# homeboard6.net
KiCad netlist of a schematic drawn in EAGLE
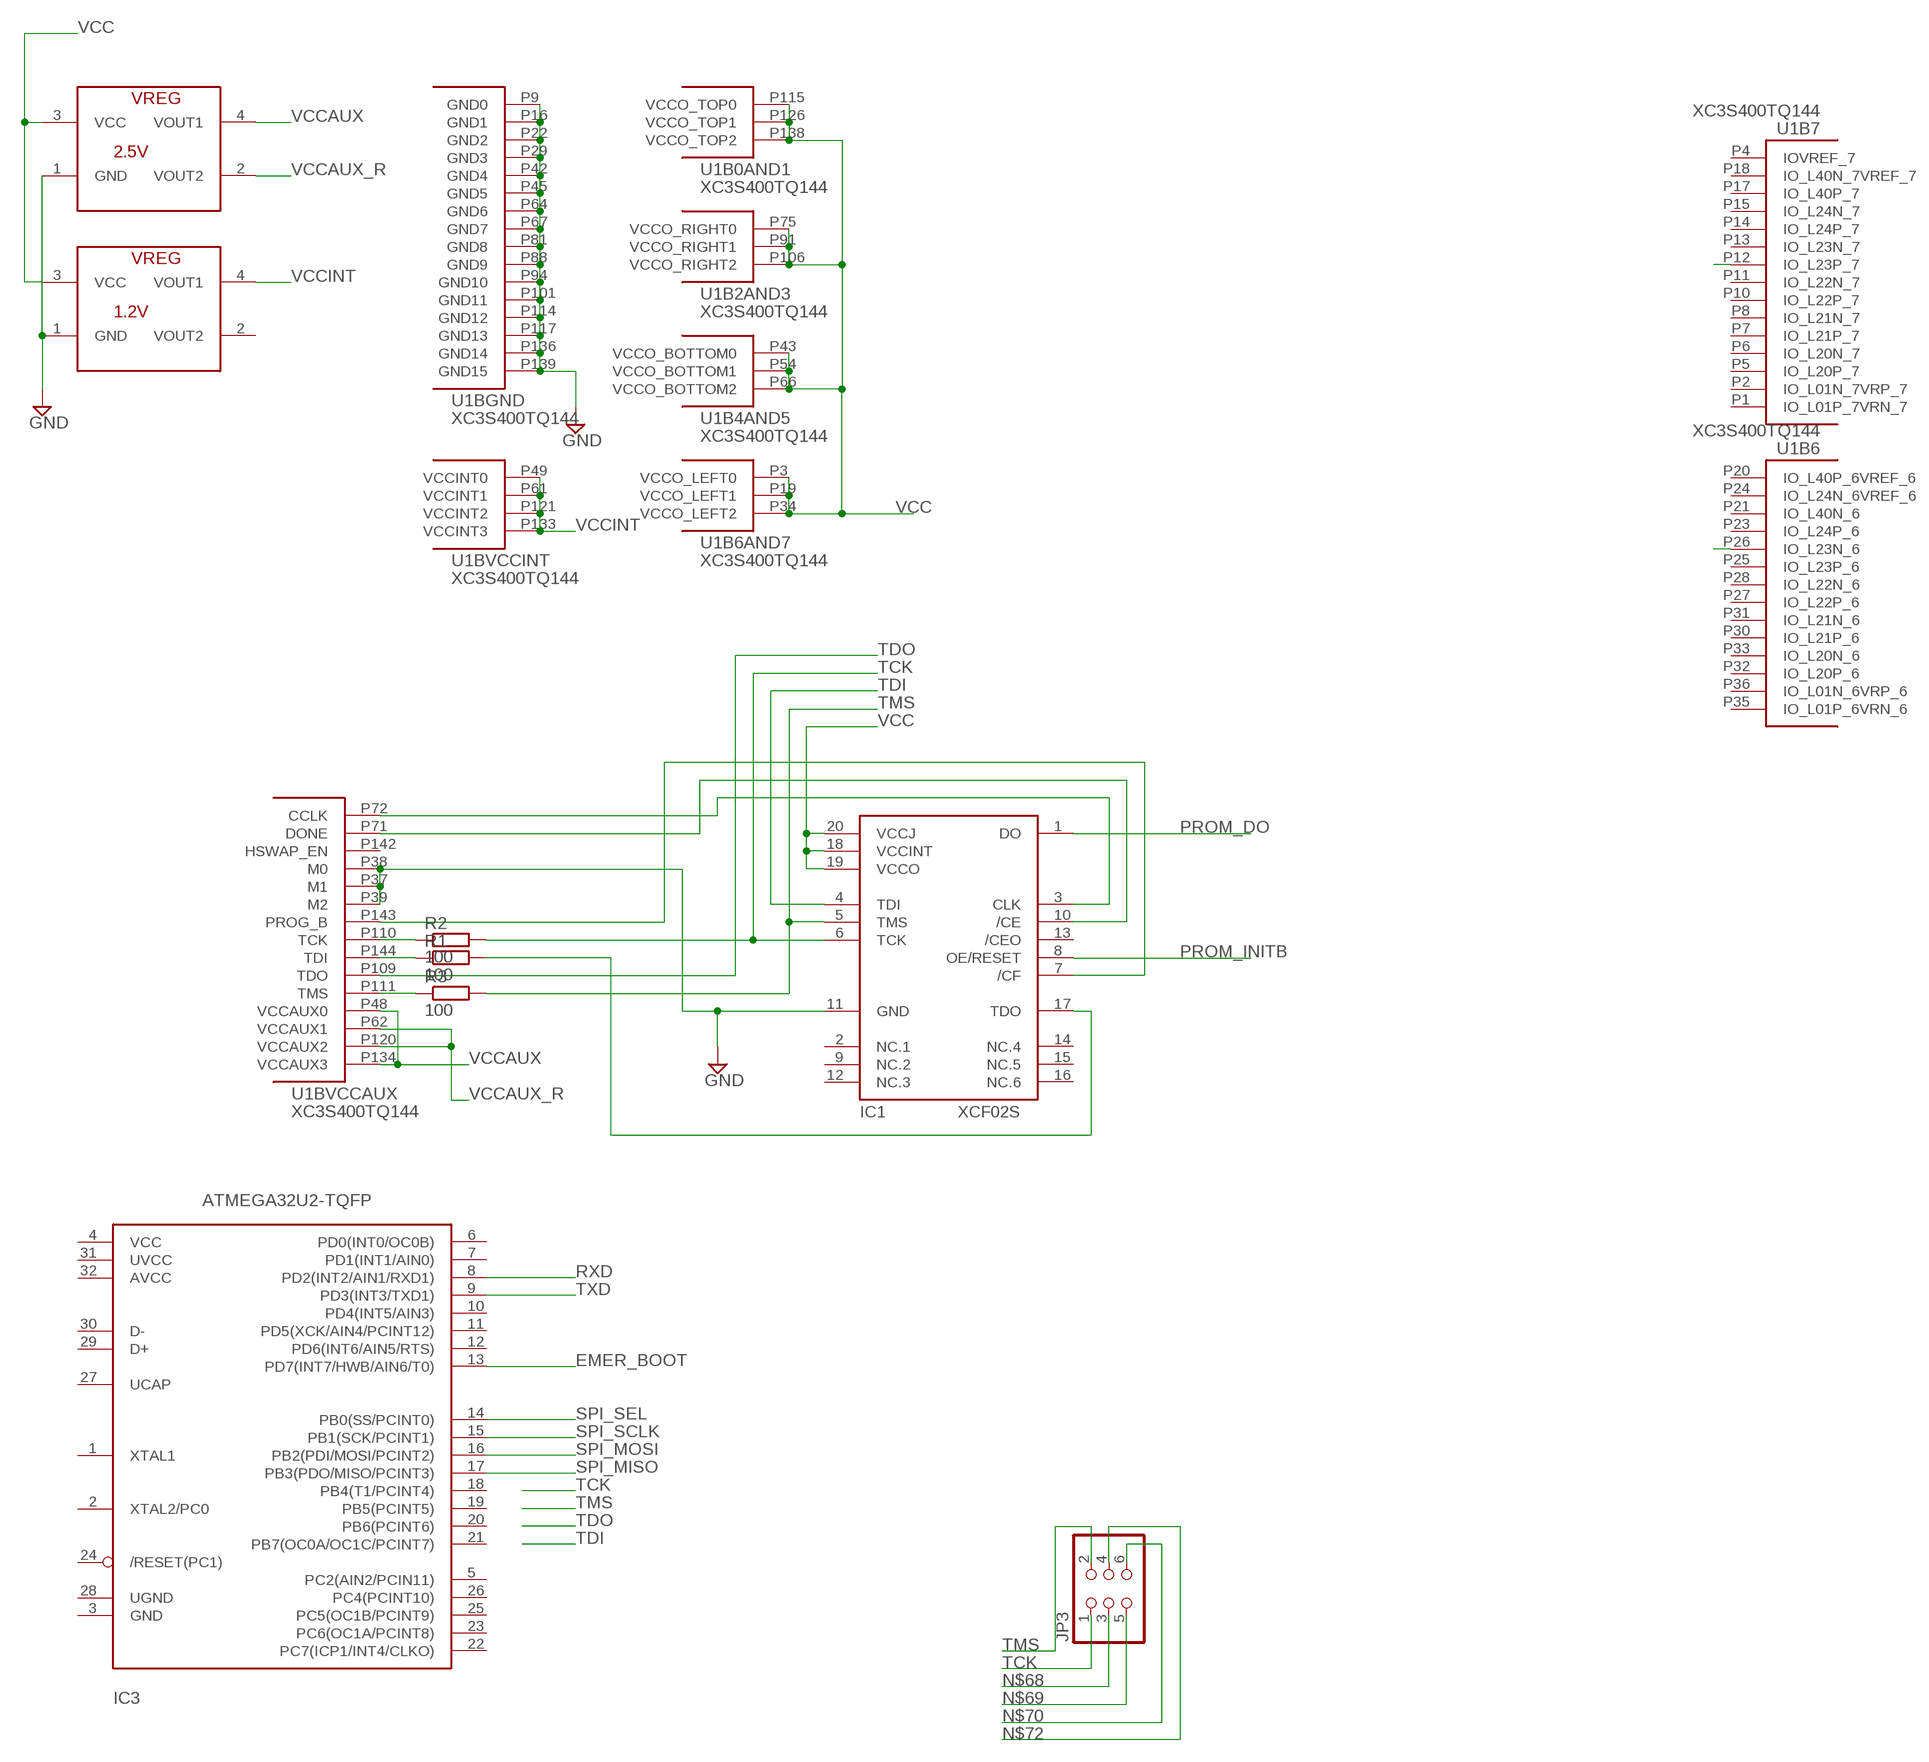
[diagram p0: schematic, sheet 1, part 1 of 3]
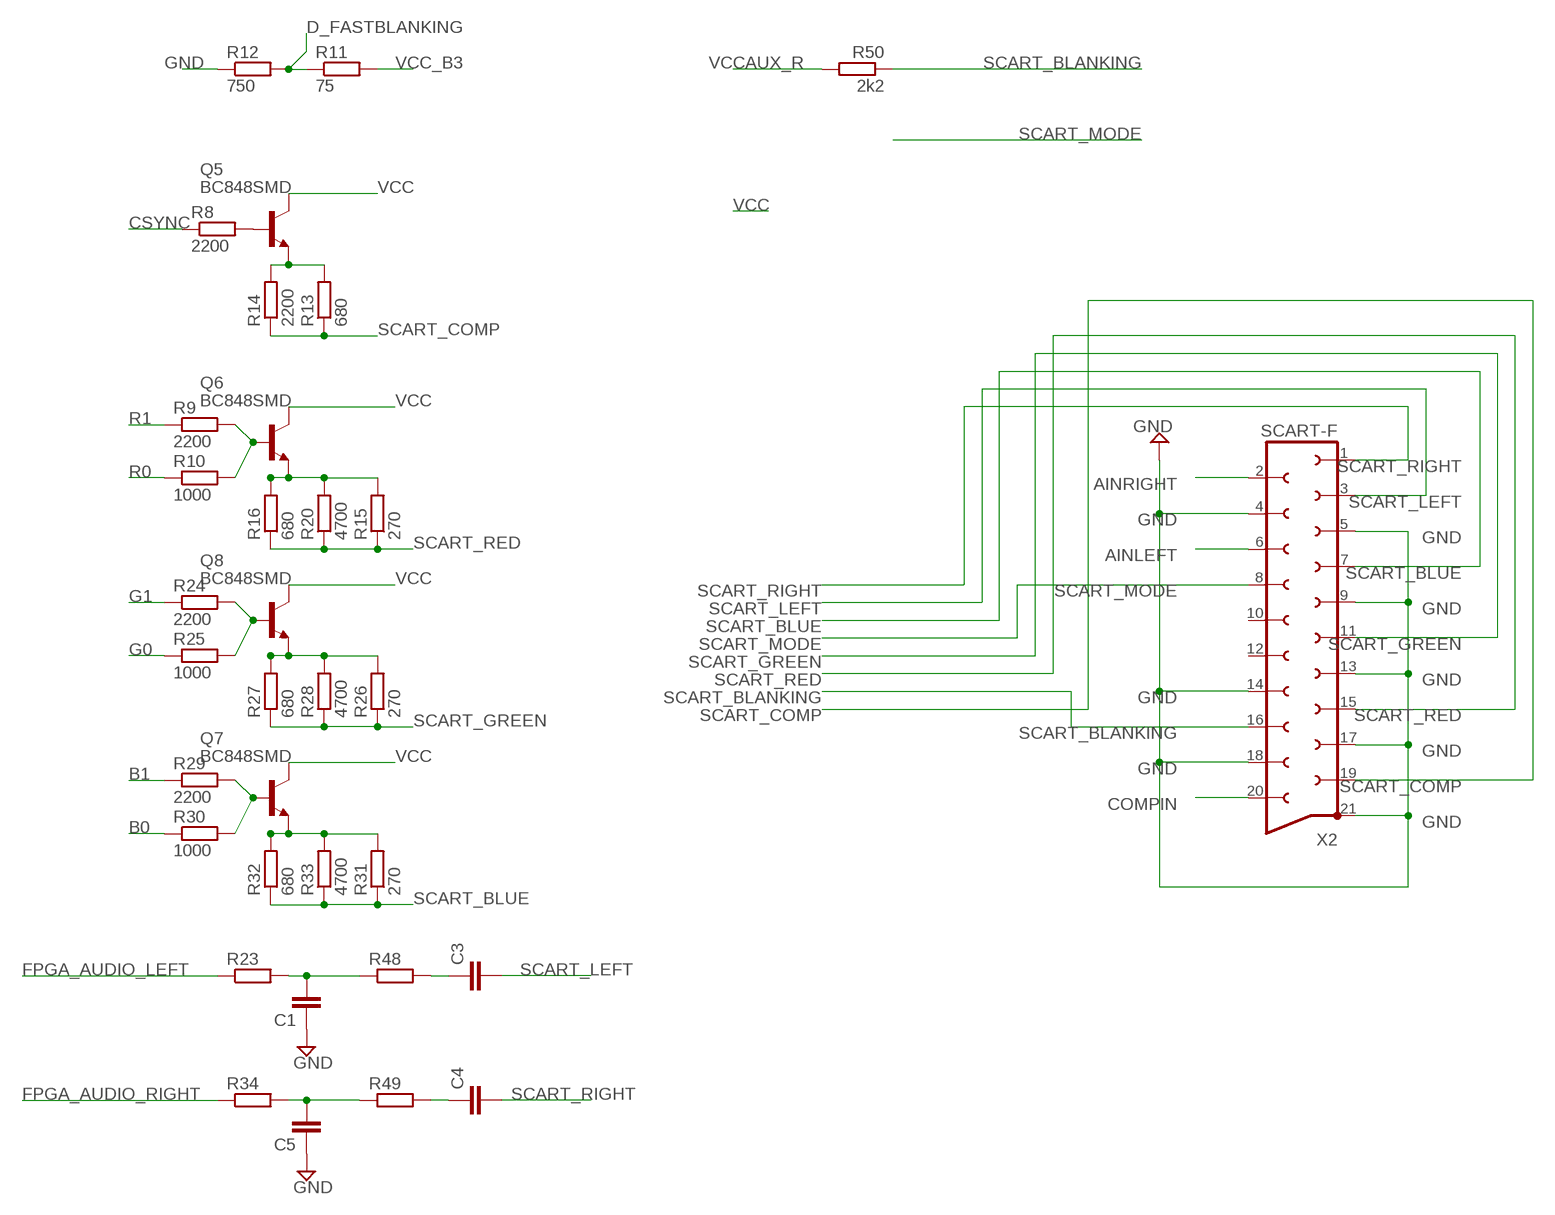
[diagram p1: schematic, sheet 1, part 2 of 3]
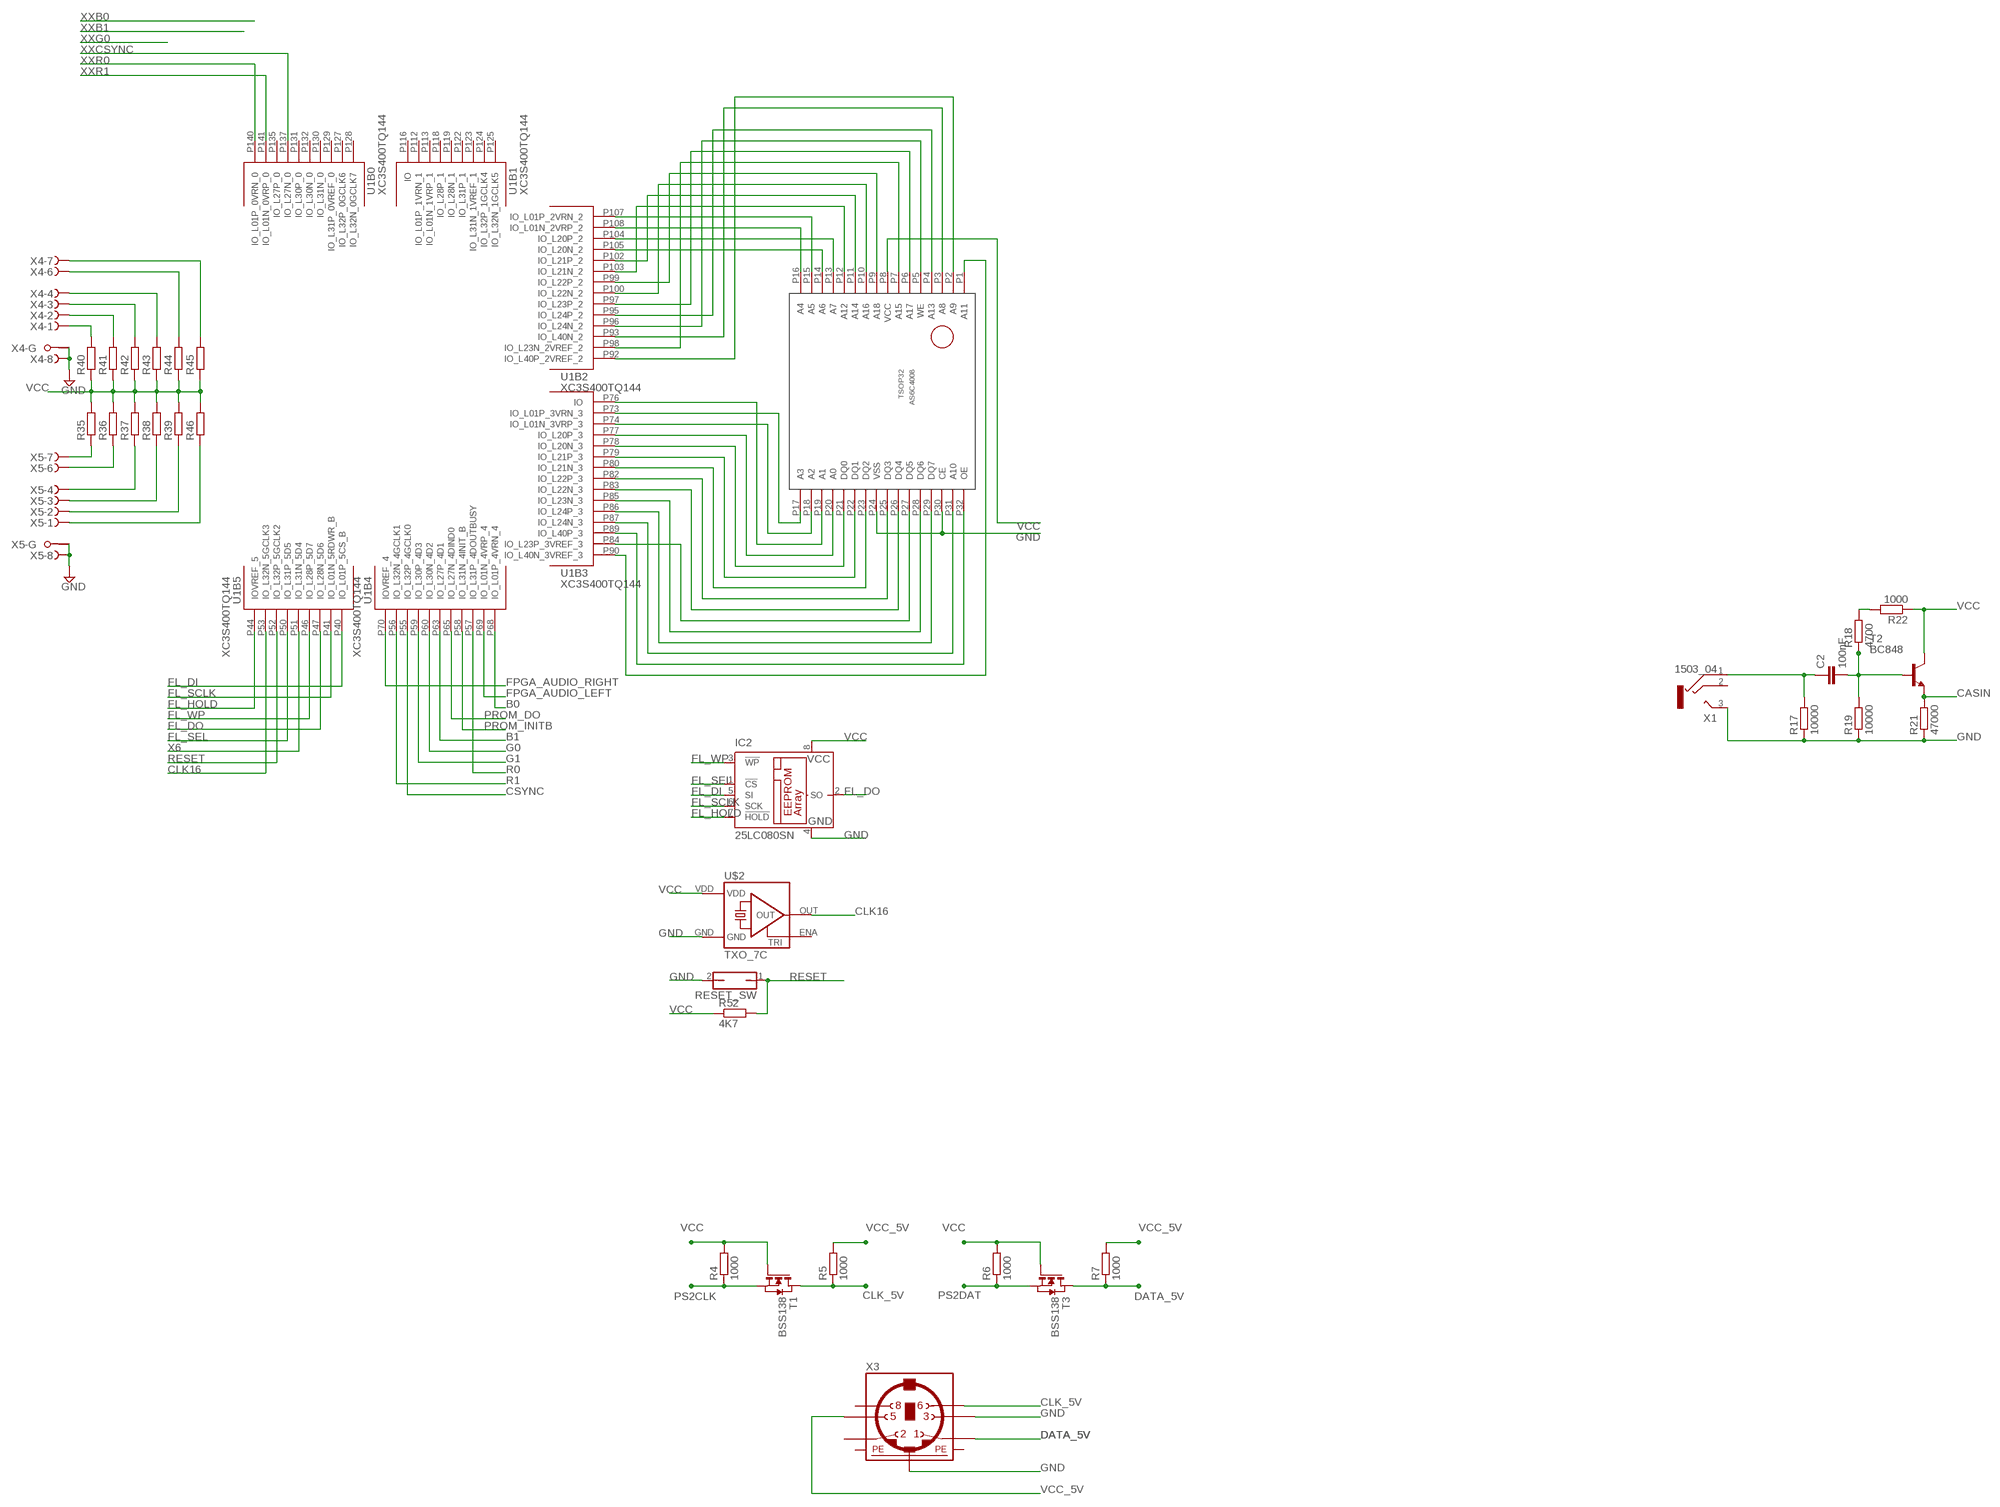
[diagram p2: schematic, sheet 1, part 3 of 3]

(export (version "E")
  (design (tool "Eeschema 10.0.6"))
  (components
    (comp (ref "C1")
      (value "C-EUC0603")
      (footprint "eagle-import:C0603")
      (libsource (lib "eagle-import") (part "C-EUC0603"))
    )
    (comp (ref "C2")
      (value "100nF")
      (footprint "eagle-import:C0603")
      (libsource (lib "eagle-import") (part "C-EUC0603"))
    )
    (comp (ref "C3")
      (value "C-EUC0603")
      (footprint "eagle-import:C0603")
      (libsource (lib "eagle-import") (part "C-EUC0603"))
    )
    (comp (ref "C4")
      (value "C-EUC0603")
      (footprint "eagle-import:C0603")
      (libsource (lib "eagle-import") (part "C-EUC0603"))
    )
    (comp (ref "C5")
      (value "C-EUC0603")
      (footprint "eagle-import:C0603")
      (libsource (lib "eagle-import") (part "C-EUC0603"))
    )
    (comp (ref "IC1")
      (value "XCF02S")
      (footprint "eagle-import:VO20")
      (libsource (lib "eagle-import") (part "XCF02S"))
    )
    (comp (ref "IC2")
      (value "25LC080SN")
      (footprint "eagle-import:SO-08")
      (fields (field (name "MF") "MICROCHIP") (field (name "MPN") "25LC080/SN"))
      (libsource (lib "eagle-import") (part "25SNLC080"))
    )
    (comp (ref "IC3")
      (value "ATMEGA32U2-TQFP")
      (footprint "eagle-import:TQFP32-08")
      (libsource (lib "eagle-import") (part "ATMEGA32U2-TQFP"))
    )
    (comp (ref "JP3")
      (value "PINHD-2X3")
      (footprint "eagle-import:2X03")
      (libsource (lib "eagle-import") (part "PINHD-2X3"))
    )
    (comp (ref "Q5")
      (value "BC848SMD")
      (footprint "eagle-import:SOT23")
      (libsource (lib "eagle-import") (part "BC848SMD"))
    )
    (comp (ref "Q6")
      (value "BC848SMD")
      (footprint "eagle-import:SOT23")
      (libsource (lib "eagle-import") (part "BC848SMD"))
    )
    (comp (ref "Q7")
      (value "BC848SMD")
      (footprint "eagle-import:SOT23")
      (libsource (lib "eagle-import") (part "BC848SMD"))
    )
    (comp (ref "Q8")
      (value "BC848SMD")
      (footprint "eagle-import:SOT23")
      (libsource (lib "eagle-import") (part "BC848SMD"))
    )
    (comp (ref "R1")
      (value "100")
      (footprint "eagle-import:R0805")
      (libsource (lib "eagle-import") (part "R-EU_R0805"))
    )
    (comp (ref "R2")
      (value "100")
      (footprint "eagle-import:R0805")
      (libsource (lib "eagle-import") (part "R-EU_R0805"))
    )
    (comp (ref "R3")
      (value "100")
      (footprint "eagle-import:R0805")
      (libsource (lib "eagle-import") (part "R-EU_R0805"))
    )
    (comp (ref "R4")
      (value "1000")
      (footprint "eagle-import:R0805")
      (libsource (lib "eagle-import") (part "R-EU_R0805"))
    )
    (comp (ref "R5")
      (value "1000")
      (footprint "eagle-import:R0805")
      (libsource (lib "eagle-import") (part "R-EU_R0805"))
    )
    (comp (ref "R6")
      (value "1000")
      (footprint "eagle-import:R0805")
      (libsource (lib "eagle-import") (part "R-EU_R0805"))
    )
    (comp (ref "R7")
      (value "1000")
      (footprint "eagle-import:R0805")
      (libsource (lib "eagle-import") (part "R-EU_R0805"))
    )
    (comp (ref "R8")
      (value "2200")
      (footprint "eagle-import:R0805")
      (libsource (lib "eagle-import") (part "R-EU_R0805"))
    )
    (comp (ref "R9")
      (value "2200")
      (footprint "eagle-import:R0805")
      (libsource (lib "eagle-import") (part "R-EU_R0805"))
    )
    (comp (ref "R10")
      (value "1000")
      (footprint "eagle-import:R0805")
      (libsource (lib "eagle-import") (part "R-EU_R0805"))
    )
    (comp (ref "R11")
      (value "75")
      (footprint "eagle-import:R0805")
      (libsource (lib "eagle-import") (part "R-EU_R0805"))
    )
    (comp (ref "R12")
      (value "750")
      (footprint "eagle-import:R0805")
      (libsource (lib "eagle-import") (part "R-EU_R0805"))
    )
    (comp (ref "R13")
      (value "680")
      (footprint "eagle-import:R0805")
      (libsource (lib "eagle-import") (part "R-EU_R0805"))
    )
    (comp (ref "R14")
      (value "2200")
      (footprint "eagle-import:R0805")
      (libsource (lib "eagle-import") (part "R-EU_R0805"))
    )
    (comp (ref "R15")
      (value "270")
      (footprint "eagle-import:R0805")
      (libsource (lib "eagle-import") (part "R-EU_R0805"))
    )
    (comp (ref "R16")
      (value "680")
      (footprint "eagle-import:R0805")
      (libsource (lib "eagle-import") (part "R-EU_R0805"))
    )
    (comp (ref "R17")
      (value "10000")
      (footprint "eagle-import:R0805")
      (libsource (lib "eagle-import") (part "R-EU_R0805"))
    )
    (comp (ref "R18")
      (value "4700")
      (footprint "eagle-import:R0805")
      (libsource (lib "eagle-import") (part "R-EU_R0805"))
    )
    (comp (ref "R19")
      (value "10000")
      (footprint "eagle-import:R0805")
      (libsource (lib "eagle-import") (part "R-EU_R0805"))
    )
    (comp (ref "R20")
      (value "4700")
      (footprint "eagle-import:R0805")
      (libsource (lib "eagle-import") (part "R-EU_R0805"))
    )
    (comp (ref "R21")
      (value "47000")
      (footprint "eagle-import:R0805")
      (libsource (lib "eagle-import") (part "R-EU_R0805"))
    )
    (comp (ref "R22")
      (value "1000")
      (footprint "eagle-import:R0805")
      (libsource (lib "eagle-import") (part "R-EU_R0805"))
    )
    (comp (ref "R23")
      (value "R-EU_M0805")
      (footprint "eagle-import:M0805")
      (libsource (lib "eagle-import") (part "resistor_R-EU_M0805"))
    )
    (comp (ref "R24")
      (value "2200")
      (footprint "eagle-import:R0805")
      (libsource (lib "eagle-import") (part "R-EU_R0805"))
    )
    (comp (ref "R25")
      (value "1000")
      (footprint "eagle-import:R0805")
      (libsource (lib "eagle-import") (part "R-EU_R0805"))
    )
    (comp (ref "R26")
      (value "270")
      (footprint "eagle-import:R0805")
      (libsource (lib "eagle-import") (part "R-EU_R0805"))
    )
    (comp (ref "R27")
      (value "680")
      (footprint "eagle-import:R0805")
      (libsource (lib "eagle-import") (part "R-EU_R0805"))
    )
    (comp (ref "R28")
      (value "4700")
      (footprint "eagle-import:R0805")
      (libsource (lib "eagle-import") (part "R-EU_R0805"))
    )
    (comp (ref "R29")
      (value "2200")
      (footprint "eagle-import:R0805")
      (libsource (lib "eagle-import") (part "R-EU_R0805"))
    )
    (comp (ref "R30")
      (value "1000")
      (footprint "eagle-import:R0805")
      (libsource (lib "eagle-import") (part "R-EU_R0805"))
    )
    (comp (ref "R31")
      (value "270")
      (footprint "eagle-import:R0805")
      (libsource (lib "eagle-import") (part "R-EU_R0805"))
    )
    (comp (ref "R32")
      (value "680")
      (footprint "eagle-import:R0805")
      (libsource (lib "eagle-import") (part "R-EU_R0805"))
    )
    (comp (ref "R33")
      (value "4700")
      (footprint "eagle-import:R0805")
      (libsource (lib "eagle-import") (part "R-EU_R0805"))
    )
    (comp (ref "R34")
      (value "R-EU_M0805")
      (footprint "eagle-import:M0805")
      (libsource (lib "eagle-import") (part "resistor_R-EU_M0805"))
    )
    (comp (ref "R35")
      (value "R-EU_M0805")
      (footprint "eagle-import:M0805")
      (libsource (lib "eagle-import") (part "resistor_R-EU_M0805"))
    )
    (comp (ref "R36")
      (value "R-EU_M0805")
      (footprint "eagle-import:M0805")
      (libsource (lib "eagle-import") (part "resistor_R-EU_M0805"))
    )
    (comp (ref "R37")
      (value "R-EU_M0805")
      (footprint "eagle-import:M0805")
      (libsource (lib "eagle-import") (part "resistor_R-EU_M0805"))
    )
    (comp (ref "R38")
      (value "R-EU_M0805")
      (footprint "eagle-import:M0805")
      (libsource (lib "eagle-import") (part "resistor_R-EU_M0805"))
    )
    (comp (ref "R39")
      (value "R-EU_M0805")
      (footprint "eagle-import:M0805")
      (libsource (lib "eagle-import") (part "resistor_R-EU_M0805"))
    )
    (comp (ref "R40")
      (value "R-EU_M0805")
      (footprint "eagle-import:M0805")
      (libsource (lib "eagle-import") (part "resistor_R-EU_M0805"))
    )
    (comp (ref "R41")
      (value "R-EU_M0805")
      (footprint "eagle-import:M0805")
      (libsource (lib "eagle-import") (part "resistor_R-EU_M0805"))
    )
    (comp (ref "R42")
      (value "R-EU_M0805")
      (footprint "eagle-import:M0805")
      (libsource (lib "eagle-import") (part "resistor_R-EU_M0805"))
    )
    (comp (ref "R43")
      (value "R-EU_M0805")
      (footprint "eagle-import:M0805")
      (libsource (lib "eagle-import") (part "resistor_R-EU_M0805"))
    )
    (comp (ref "R44")
      (value "R-EU_M0805")
      (footprint "eagle-import:M0805")
      (libsource (lib "eagle-import") (part "resistor_R-EU_M0805"))
    )
    (comp (ref "R45")
      (value "R-EU_M0805")
      (footprint "eagle-import:M0805")
      (libsource (lib "eagle-import") (part "resistor_R-EU_M0805"))
    )
    (comp (ref "R46")
      (value "R-EU_M0805")
      (footprint "eagle-import:M0805")
      (libsource (lib "eagle-import") (part "resistor_R-EU_M0805"))
    )
    (comp (ref "R48")
      (value "R-EU_M0805")
      (footprint "eagle-import:M0805")
      (libsource (lib "eagle-import") (part "resistor_R-EU_M0805"))
    )
    (comp (ref "R49")
      (value "R-EU_M0805")
      (footprint "eagle-import:M0805")
      (libsource (lib "eagle-import") (part "resistor_R-EU_M0805"))
    )
    (comp (ref "R50")
      (value "2k2")
      (footprint "eagle-import:M0805")
      (libsource (lib "eagle-import") (part "resistor_R-EU_M0805"))
    )
    (comp (ref "R52")
      (value "4K7")
      (footprint "eagle-import:M0805")
      (libsource (lib "eagle-import") (part "resistor_R-EU_M0805"))
    )
    (comp (ref "REG1.2")
      (value "1.2V")
      (footprint "eagle-import:SOT223")
      (libsource (lib "eagle-import") (part "NX1117"))
    )
    (comp (ref "REG2.5")
      (value "2.5V")
      (footprint "eagle-import:SOT223")
      (libsource (lib "eagle-import") (part "NX1117"))
    )
    (comp (ref "RESET_SW")
      (value "JP1Q")
      (footprint "eagle-import:JP1")
      (libsource (lib "eagle-import") (part "JP1Q"))
    )
    (comp (ref "T1")
      (value "BSS138")
      (footprint "eagle-import:SOT-23")
      (libsource (lib "eagle-import") (part "NMOSSOT23"))
    )
    (comp (ref "T2")
      (value "BC848")
      (footprint "eagle-import:SOT23")
      (libsource (lib "eagle-import") (part "BC848"))
    )
    (comp (ref "T3")
      (value "BSS138")
      (footprint "eagle-import:SOT-23")
      (libsource (lib "eagle-import") (part "NMOSSOT23"))
    )
    (comp (ref "U$1")
      (value "AS6C4008")
      (footprint "eagle-import:TSOP32")
      (libsource (lib "eagle-import") (part "AS6C4008"))
    )
    (comp (ref "U$2")
      (value "TXO_7C")
      (footprint "eagle-import:OSC_7C")
      (libsource (lib "eagle-import") (part "TXO_7C"))
    )
    (comp (ref "U1")
      (value "XC3S400TQ144")
      (footprint "eagle-import:TQ144")
      (libsource (lib "eagle-import") (part "XC3S400TQ144"))
    )
    (comp (ref "X1")
      (value "1503_04")
      (footprint "eagle-import:1503_04")
      (libsource (lib "eagle-import") (part "1503_04"))
    )
    (comp (ref "X2")
      (value "SCART-F")
      (footprint "eagle-import:SCART-F")
      (libsource (lib "eagle-import") (part "SCART-F"))
    )
    (comp (ref "X3")
      (value "MINI_DIN_6")
      (footprint "eagle-import:M_DIN6")
      (libsource (lib "eagle-import") (part "MINI_DIN_6"))
    )
    (comp (ref "X4")
      (value "F09HPS")
      (footprint "eagle-import:F09HP")
      (libsource (lib "eagle-import") (part "F09HPS"))
    )
    (comp (ref "X5")
      (value "F09HPS")
      (footprint "eagle-import:F09HP")
      (libsource (lib "eagle-import") (part "F09HPS"))
    )
  )
  (nets
    (net (code "1") (name "/AINLEFT") (class "Default")
      (node (ref "X2") (pin "6") (pinfunction "6_6") (pintype "passive"))
    )
    (net (code "2") (name "/AINRIGHT") (class "Default")
      (node (ref "X2") (pin "2") (pinfunction "2_2") (pintype "passive"))
    )
    (net (code "3") (name "/B0") (class "Default")
      (node (ref "R30") (pin "1") (pinfunction "1_1") (pintype "passive"))
      (node (ref "U1") (pin "P68") (pinfunction "IO_L01P_4VRN_4_P68") (pintype "bidirectional"))
    )
    (net (code "4") (name "/B1") (class "Default")
      (node (ref "R29") (pin "1") (pinfunction "1_1") (pintype "passive"))
      (node (ref "U1") (pin "P63") (pinfunction "IO_L27P_4D1_P63") (pintype "bidirectional"))
    )
    (net (code "5") (name "/CASIN") (class "Default")
      (node (ref "R21") (pin "2") (pinfunction "2_2") (pintype "passive"))
      (node (ref "T2") (pin "2") (pinfunction "E_2") (pintype "passive"))
    )
    (net (code "6") (name "/CLK16") (class "Default")
      (node (ref "U$2") (pin "OUT") (pinfunction "OUT_OUT") (pintype "output"))
      (node (ref "U1") (pin "P53") (pinfunction "IO_L32N_5GCLK3_P53") (pintype "bidirectional"))
    )
    (net (code "7") (name "/CLK_5V") (class "Default")
      (node (ref "R5") (pin "1") (pinfunction "1_1") (pintype "passive"))
      (node (ref "T1") (pin "1") (pinfunction "D_1") (pintype "passive"))
      (node (ref "X3") (pin "6") (pinfunction "6_6") (pintype "passive"))
    )
    (net (code "8") (name "/COMPIN") (class "Default")
      (node (ref "X2") (pin "20") (pinfunction "20_20") (pintype "passive"))
    )
    (net (code "9") (name "/CSYNC") (class "Default")
      (node (ref "R8") (pin "1") (pinfunction "1_1") (pintype "passive"))
      (node (ref "U1") (pin "P55") (pinfunction "IO_L32P_4GCLK0_P55") (pintype "bidirectional"))
    )
    (net (code "10") (name "/DATA_5V") (class "Default")
      (node (ref "R7") (pin "1") (pinfunction "1_1") (pintype "passive"))
      (node (ref "T3") (pin "1") (pinfunction "D_1") (pintype "passive"))
      (node (ref "X3") (pin "1") (pinfunction "1_1") (pintype "passive"))
    )
    (net (code "11") (name "/D_FASTBLANKING") (class "Default")
      (node (ref "R11") (pin "1") (pinfunction "1_1") (pintype "passive"))
      (node (ref "R12") (pin "2") (pinfunction "2_2") (pintype "passive"))
    )
    (net (code "12") (name "/EMER_BOOT") (class "Default")
      (node (ref "IC3") (pin "13") (pinfunction "PD7(INT7/HWB/AIN6/T0)_13") (pintype "bidirectional"))
    )
    (net (code "13") (name "/FL_DI") (class "Default")
      (node (ref "IC2") (pin "5") (pinfunction "SI_5") (pintype "input"))
      (node (ref "U1") (pin "P40") (pinfunction "IO_L01P_5CS_B_P40") (pintype "bidirectional"))
    )
    (net (code "14") (name "/FL_DO") (class "Default")
      (node (ref "IC2") (pin "2") (pinfunction "SO_2") (pintype "bidirectional"))
      (node (ref "U1") (pin "P47") (pinfunction "IO_L28N_5D6_P47") (pintype "bidirectional"))
    )
    (net (code "15") (name "/FL_HOLD") (class "Default")
      (node (ref "IC2") (pin "7") (pinfunction "~{HOLD}_7") (pintype "input"))
      (node (ref "U1") (pin "P44") (pinfunction "IOVREF_5_P44") (pintype "bidirectional"))
    )
    (net (code "16") (name "/FL_SCLK") (class "Default")
      (node (ref "IC2") (pin "6") (pinfunction "SCK_6") (pintype "input"))
      (node (ref "U1") (pin "P41") (pinfunction "IO_L01N_5RDWR_B_P41") (pintype "bidirectional"))
    )
    (net (code "17") (name "/FL_SEL") (class "Default")
      (node (ref "IC2") (pin "1") (pinfunction "~{CS}_1") (pintype "input"))
      (node (ref "U1") (pin "P50") (pinfunction "IO_L31P_5D5_P50") (pintype "bidirectional"))
    )
    (net (code "18") (name "/FL_WP") (class "Default")
      (node (ref "IC2") (pin "3") (pinfunction "~{WP}_3") (pintype "input"))
      (node (ref "U1") (pin "P46") (pinfunction "IO_L28P_5D7_P46") (pintype "bidirectional"))
    )
    (net (code "19") (name "/FPGA_AUDIO_LEFT") (class "Default")
      (node (ref "R23") (pin "1") (pinfunction "1_1") (pintype "passive"))
      (node (ref "U1") (pin "P69") (pinfunction "IO_L01N_4VRP_4_P69") (pintype "bidirectional"))
    )
    (net (code "20") (name "/FPGA_AUDIO_RIGHT") (class "Default")
      (node (ref "R34") (pin "1") (pinfunction "1_1") (pintype "passive"))
      (node (ref "U1") (pin "P70") (pinfunction "IOVREF_4_P70") (pintype "bidirectional"))
    )
    (net (code "21") (name "/G0") (class "Default")
      (node (ref "R25") (pin "1") (pinfunction "1_1") (pintype "passive"))
      (node (ref "U1") (pin "P60") (pinfunction "IO_L30N_4D2_P60") (pintype "bidirectional"))
    )
    (net (code "22") (name "/G1") (class "Default")
      (node (ref "R24") (pin "1") (pinfunction "1_1") (pintype "passive"))
      (node (ref "U1") (pin "P59") (pinfunction "IO_L30P_4D3_P59") (pintype "bidirectional"))
    )
    (net (code "23") (name "/N$68") (class "Default")
      (node (ref "JP3") (pin "3") (pinfunction "3_3") (pintype "passive"))
    )
    (net (code "24") (name "/N$69") (class "Default")
      (node (ref "JP3") (pin "5") (pinfunction "5_5") (pintype "passive"))
    )
    (net (code "25") (name "/N$70") (class "Default")
      (node (ref "JP3") (pin "6") (pinfunction "6_6") (pintype "passive"))
    )
    (net (code "26") (name "/N$72") (class "Default")
      (node (ref "JP3") (pin "4") (pinfunction "4_4") (pintype "passive"))
    )
    (net (code "27") (name "/PE1") (class "Default")
      (node (ref "X3") (pin "SH1") (pinfunction "PE1_SH1") (pintype "power_in"))
    )
    (net (code "28") (name "/PE3") (class "Default")
      (node (ref "X3") (pin "SH3") (pinfunction "PE3_SH3") (pintype "power_in"))
    )
    (net (code "29") (name "/PROM_DO") (class "Default")
      (node (ref "IC1") (pin "1") (pinfunction "DO_1") (pintype "bidirectional"))
      (node (ref "U1") (pin "P65") (pinfunction "IO_L27N_4DIND0_P65") (pintype "bidirectional"))
    )
    (net (code "30") (name "/PROM_INITB") (class "Default")
      (node (ref "IC1") (pin "8") (pinfunction "OE/RESET_8") (pintype "bidirectional"))
      (node (ref "U1") (pin "P58") (pinfunction "IO_L31N_4INIT_B_P58") (pintype "bidirectional"))
    )
    (net (code "31") (name "/PS2CLK") (class "Default")
      (node (ref "R4") (pin "1") (pinfunction "1_1") (pintype "passive"))
      (node (ref "T1") (pin "2") (pinfunction "S_2") (pintype "passive"))
    )
    (net (code "32") (name "/PS2DAT") (class "Default")
      (node (ref "R6") (pin "1") (pinfunction "1_1") (pintype "passive"))
      (node (ref "T3") (pin "2") (pinfunction "S_2") (pintype "passive"))
    )
    (net (code "33") (name "/R0") (class "Default")
      (node (ref "R10") (pin "1") (pinfunction "1_1") (pintype "passive"))
      (node (ref "U1") (pin "P57") (pinfunction "IO_L31P_4DOUTBUSY_P57") (pintype "bidirectional"))
    )
    (net (code "34") (name "/R1") (class "Default")
      (node (ref "R9") (pin "1") (pinfunction "1_1") (pintype "passive"))
      (node (ref "U1") (pin "P56") (pinfunction "IO_L32N_4GCLK1_P56") (pintype "bidirectional"))
    )
    (net (code "35") (name "/RESET") (class "Default")
      (node (ref "R52") (pin "2") (pinfunction "2_2") (pintype "passive"))
      (node (ref "RESET_SW") (pin "1") (pinfunction "1_1") (pintype "passive"))
      (node (ref "U1") (pin "P52") (pinfunction "IO_L32P_5GCLK2_P52") (pintype "bidirectional"))
    )
    (net (code "36") (name "/RXD") (class "Default")
      (node (ref "IC3") (pin "8") (pinfunction "PD2(INT2/AIN1/RXD1)_8") (pintype "bidirectional"))
    )
    (net (code "37") (name "/SCART_BLANKING") (class "Default")
      (node (ref "R50") (pin "1") (pinfunction "1_1") (pintype "passive"))
      (node (ref "X2") (pin "16") (pinfunction "16_16") (pintype "passive"))
    )
    (net (code "38") (name "/SCART_BLUE") (class "Default")
      (node (ref "R31") (pin "1") (pinfunction "1_1") (pintype "passive"))
      (node (ref "R32") (pin "1") (pinfunction "1_1") (pintype "passive"))
      (node (ref "R33") (pin "1") (pinfunction "1_1") (pintype "passive"))
      (node (ref "X2") (pin "7") (pinfunction "7_7") (pintype "passive"))
    )
    (net (code "39") (name "/SCART_COMP") (class "Default")
      (node (ref "R13") (pin "1") (pinfunction "1_1") (pintype "passive"))
      (node (ref "R14") (pin "1") (pinfunction "1_1") (pintype "passive"))
      (node (ref "X2") (pin "19") (pinfunction "19_19") (pintype "passive"))
    )
    (net (code "40") (name "/SCART_GREEN") (class "Default")
      (node (ref "R26") (pin "1") (pinfunction "1_1") (pintype "passive"))
      (node (ref "R27") (pin "1") (pinfunction "1_1") (pintype "passive"))
      (node (ref "R28") (pin "1") (pinfunction "1_1") (pintype "passive"))
      (node (ref "X2") (pin "11") (pinfunction "11_11") (pintype "passive"))
    )
    (net (code "41") (name "/SCART_LEFT") (class "Default")
      (node (ref "C3") (pin "2") (pinfunction "2_2") (pintype "passive"))
      (node (ref "X2") (pin "3") (pinfunction "3_3") (pintype "passive"))
    )
    (net (code "42") (name "/SCART_MODE") (class "Default")
      (node (ref "X2") (pin "8") (pinfunction "8_8") (pintype "passive"))
    )
    (net (code "43") (name "/SCART_RED") (class "Default")
      (node (ref "R15") (pin "1") (pinfunction "1_1") (pintype "passive"))
      (node (ref "R16") (pin "1") (pinfunction "1_1") (pintype "passive"))
      (node (ref "R20") (pin "1") (pinfunction "1_1") (pintype "passive"))
      (node (ref "X2") (pin "15") (pinfunction "15_15") (pintype "passive"))
    )
    (net (code "44") (name "/SCART_RIGHT") (class "Default")
      (node (ref "C4") (pin "2") (pinfunction "2_2") (pintype "passive"))
      (node (ref "X2") (pin "1") (pinfunction "1_1") (pintype "passive"))
    )
    (net (code "45") (name "/SPI_MISO") (class "Default")
      (node (ref "IC3") (pin "17") (pinfunction "PB3(PDO/MISO/PCINT3)_17") (pintype "bidirectional"))
    )
    (net (code "46") (name "/SPI_MOSI") (class "Default")
      (node (ref "IC3") (pin "16") (pinfunction "PB2(PDI/MOSI/PCINT2)_16") (pintype "bidirectional"))
    )
    (net (code "47") (name "/SPI_SCLK") (class "Default")
      (node (ref "IC3") (pin "15") (pinfunction "PB1(SCK/PCINT1)_15") (pintype "bidirectional"))
    )
    (net (code "48") (name "/SPI_SEL") (class "Default")
      (node (ref "IC3") (pin "14") (pinfunction "PB0(SS/PCINT0)_14") (pintype "bidirectional"))
    )
    (net (code "49") (name "/TCK") (class "Default")
      (node (ref "IC1") (pin "6") (pinfunction "TCK_6") (pintype "bidirectional"))
      (node (ref "JP3") (pin "1") (pinfunction "1_1") (pintype "passive"))
      (node (ref "R2") (pin "2") (pinfunction "2_2") (pintype "passive"))
    )
    (net (code "50") (name "/TDI") (class "Default")
      (node (ref "IC1") (pin "4") (pinfunction "TDI_4") (pintype "bidirectional"))
    )
    (net (code "51") (name "/TDO") (class "Default")
      (node (ref "U1") (pin "P109") (pinfunction "TDO_P109") (pintype "bidirectional"))
    )
    (net (code "52") (name "/TMS") (class "Default")
      (node (ref "IC1") (pin "5") (pinfunction "TMS_5") (pintype "bidirectional"))
      (node (ref "JP3") (pin "2") (pinfunction "2_2") (pintype "passive"))
      (node (ref "R3") (pin "2") (pinfunction "2_2") (pintype "passive"))
    )
    (net (code "53") (name "/TXD") (class "Default")
      (node (ref "IC3") (pin "9") (pinfunction "PD3(INT3/TXD1)_9") (pintype "bidirectional"))
    )
    (net (code "54") (name "/VCC") (class "Default")
      (node (ref "IC1") (pin "18") (pinfunction "VCCINT_18") (pintype "bidirectional"))
      (node (ref "IC1") (pin "19") (pinfunction "VCCO_19") (pintype "bidirectional"))
      (node (ref "IC1") (pin "20") (pinfunction "VCCJ_20") (pintype "bidirectional"))
      (node (ref "IC2") (pin "8") (pinfunction "VCC_8") (pintype "power_in"))
      (node (ref "Q5") (pin "3") (pinfunction "C_3") (pintype "passive"))
      (node (ref "Q6") (pin "3") (pinfunction "C_3") (pintype "passive"))
      (node (ref "Q7") (pin "3") (pinfunction "C_3") (pintype "passive"))
      (node (ref "Q8") (pin "3") (pinfunction "C_3") (pintype "passive"))
      (node (ref "R22") (pin "1") (pinfunction "1_1") (pintype "passive"))
      (node (ref "R35") (pin "2") (pinfunction "2_2") (pintype "passive"))
      (node (ref "R36") (pin "2") (pinfunction "2_2") (pintype "passive"))
      (node (ref "R37") (pin "2") (pinfunction "2_2") (pintype "passive"))
      (node (ref "R38") (pin "2") (pinfunction "2_2") (pintype "passive"))
      (node (ref "R39") (pin "2") (pinfunction "2_2") (pintype "passive"))
      (node (ref "R4") (pin "2") (pinfunction "2_2") (pintype "passive"))
      (node (ref "R40") (pin "1") (pinfunction "1_1") (pintype "passive"))
      (node (ref "R41") (pin "1") (pinfunction "1_1") (pintype "passive"))
      (node (ref "R42") (pin "1") (pinfunction "1_1") (pintype "passive"))
      (node (ref "R43") (pin "1") (pinfunction "1_1") (pintype "passive"))
      (node (ref "R44") (pin "1") (pinfunction "1_1") (pintype "passive"))
      (node (ref "R45") (pin "1") (pinfunction "1_1") (pintype "passive"))
      (node (ref "R46") (pin "2") (pinfunction "2_2") (pintype "passive"))
      (node (ref "R52") (pin "1") (pinfunction "1_1") (pintype "passive"))
      (node (ref "R6") (pin "2") (pinfunction "2_2") (pintype "passive"))
      (node (ref "REG1.2") (pin "3") (pinfunction "VCC_3") (pintype "bidirectional"))
      (node (ref "REG2.5") (pin "3") (pinfunction "VCC_3") (pintype "bidirectional"))
      (node (ref "T1") (pin "3") (pinfunction "G_3") (pintype "passive"))
      (node (ref "T2") (pin "3") (pinfunction "C_3") (pintype "passive"))
      (node (ref "T3") (pin "3") (pinfunction "G_3") (pintype "passive"))
      (node (ref "U$1") (pin "P8") (pinfunction "VCC_P8") (pintype "bidirectional"))
      (node (ref "U$2") (pin "VDD") (pinfunction "VDD_VDD") (pintype "power_in"))
      (node (ref "U1") (pin "P106") (pinfunction "VCCO_RIGHT2_P106") (pintype "passive"))
      (node (ref "U1") (pin "P115") (pinfunction "VCCO_TOP0_P115") (pintype "passive"))
      (node (ref "U1") (pin "P126") (pinfunction "VCCO_TOP1_P126") (pintype "passive"))
      (node (ref "U1") (pin "P138") (pinfunction "VCCO_TOP2_P138") (pintype "passive"))
      (node (ref "U1") (pin "P19") (pinfunction "VCCO_LEFT1_P19") (pintype "passive"))
      (node (ref "U1") (pin "P3") (pinfunction "VCCO_LEFT0_P3") (pintype "passive"))
      (node (ref "U1") (pin "P34") (pinfunction "VCCO_LEFT2_P34") (pintype "passive"))
      (node (ref "U1") (pin "P43") (pinfunction "VCCO_BOTTOM0_P43") (pintype "passive"))
      (node (ref "U1") (pin "P54") (pinfunction "VCCO_BOTTOM1_P54") (pintype "passive"))
      (node (ref "U1") (pin "P66") (pinfunction "VCCO_BOTTOM2_P66") (pintype "passive"))
      (node (ref "U1") (pin "P75") (pinfunction "VCCO_RIGHT0_P75") (pintype "passive"))
      (node (ref "U1") (pin "P91") (pinfunction "VCCO_RIGHT1_P91") (pintype "passive"))
    )
    (net (code "55") (name "/VCCAUX") (class "Default")
      (node (ref "REG2.5") (pin "4") (pinfunction "VOUT1_4") (pintype "bidirectional"))
      (node (ref "U1") (pin "P134") (pinfunction "VCCAUX3_P134") (pintype "passive"))
      (node (ref "U1") (pin "P48") (pinfunction "VCCAUX0_P48") (pintype "passive"))
    )
    (net (code "56") (name "/VCCAUX_R") (class "Default")
      (node (ref "R50") (pin "2") (pinfunction "2_2") (pintype "passive"))
      (node (ref "REG2.5") (pin "2") (pinfunction "VOUT2_2") (pintype "bidirectional"))
      (node (ref "U1") (pin "P120") (pinfunction "VCCAUX2_P120") (pintype "passive"))
      (node (ref "U1") (pin "P62") (pinfunction "VCCAUX1_P62") (pintype "passive"))
    )
    (net (code "57") (name "/VCCINT") (class "Default")
      (node (ref "REG1.2") (pin "4") (pinfunction "VOUT1_4") (pintype "bidirectional"))
      (node (ref "U1") (pin "P121") (pinfunction "VCCINT2_P121") (pintype "passive"))
      (node (ref "U1") (pin "P133") (pinfunction "VCCINT3_P133") (pintype "passive"))
      (node (ref "U1") (pin "P49") (pinfunction "VCCINT0_P49") (pintype "passive"))
      (node (ref "U1") (pin "P61") (pinfunction "VCCINT1_P61") (pintype "passive"))
    )
    (net (code "58") (name "/VCC_5V") (class "Default")
      (node (ref "R5") (pin "2") (pinfunction "2_2") (pintype "passive"))
      (node (ref "R7") (pin "2") (pinfunction "2_2") (pintype "passive"))
      (node (ref "X3") (pin "5") (pinfunction "5_5") (pintype "passive"))
    )
    (net (code "59") (name "/VCC_B3") (class "Default")
      (node (ref "R11") (pin "2") (pinfunction "2_2") (pintype "passive"))
    )
    (net (code "60") (name "/X6") (class "Default")
      (node (ref "U1") (pin "P51") (pinfunction "IO_L31N_5D4_P51") (pintype "bidirectional"))
    )
    (net (code "63") (name "/XXCSYNC") (class "Default")
      (node (ref "U1") (pin "P137") (pinfunction "IO_L27N_0_P137") (pintype "bidirectional"))
    )
    (net (code "65") (name "/XXR0") (class "Default")
      (node (ref "U1") (pin "P140") (pinfunction "IO_L01P_0VRN_0_P140") (pintype "bidirectional"))
    )
    (net (code "66") (name "/XXR1") (class "Default")
      (node (ref "U1") (pin "P141") (pinfunction "IO_L01N_0VRP_0_P141") (pintype "bidirectional"))
    )
    (net (code "67") (name "GND") (class "Default")
      (node (ref "C1") (pin "1") (pinfunction "1_1") (pintype "passive"))
      (node (ref "C5") (pin "1") (pinfunction "1_1") (pintype "passive"))
      (node (ref "IC1") (pin "11") (pinfunction "GND_11") (pintype "bidirectional"))
      (node (ref "IC2") (pin "4") (pinfunction "GND_4") (pintype "power_in"))
      (node (ref "R12") (pin "1") (pinfunction "1_1") (pintype "passive"))
      (node (ref "R17") (pin "1") (pinfunction "1_1") (pintype "passive"))
      (node (ref "R19") (pin "1") (pinfunction "1_1") (pintype "passive"))
      (node (ref "R21") (pin "1") (pinfunction "1_1") (pintype "passive"))
      (node (ref "REG1.2") (pin "1") (pinfunction "GND_1") (pintype "bidirectional"))
      (node (ref "REG2.5") (pin "1") (pinfunction "GND_1") (pintype "bidirectional"))
      (node (ref "RESET_SW") (pin "2") (pinfunction "2_2") (pintype "passive"))
      (node (ref "U$1") (pin "P24") (pinfunction "VSS_P24") (pintype "bidirectional"))
      (node (ref "U$1") (pin "P30") (pinfunction "CE_P30") (pintype "bidirectional"))
      (node (ref "U$2") (pin "GND") (pinfunction "GND_GND") (pintype "power_in"))
      (node (ref "U1") (pin "P101") (pinfunction "GND11_P101") (pintype "passive"))
      (node (ref "U1") (pin "P114") (pinfunction "GND12_P114") (pintype "passive"))
      (node (ref "U1") (pin "P117") (pinfunction "GND13_P117") (pintype "passive"))
      (node (ref "U1") (pin "P136") (pinfunction "GND14_P136") (pintype "passive"))
      (node (ref "U1") (pin "P139") (pinfunction "GND15_P139") (pintype "passive"))
      (node (ref "U1") (pin "P16") (pinfunction "GND1_P16") (pintype "passive"))
      (node (ref "U1") (pin "P22") (pinfunction "GND2_P22") (pintype "passive"))
      (node (ref "U1") (pin "P29") (pinfunction "GND3_P29") (pintype "passive"))
      (node (ref "U1") (pin "P37") (pinfunction "M1_P37") (pintype "bidirectional"))
      (node (ref "U1") (pin "P38") (pinfunction "M0_P38") (pintype "bidirectional"))
      (node (ref "U1") (pin "P39") (pinfunction "M2_P39") (pintype "bidirectional"))
      (node (ref "U1") (pin "P42") (pinfunction "GND4_P42") (pintype "passive"))
      (node (ref "U1") (pin "P45") (pinfunction "GND5_P45") (pintype "passive"))
      (node (ref "U1") (pin "P64") (pinfunction "GND6_P64") (pintype "passive"))
      (node (ref "U1") (pin "P67") (pinfunction "GND7_P67") (pintype "passive"))
      (node (ref "U1") (pin "P81") (pinfunction "GND8_P81") (pintype "passive"))
      (node (ref "U1") (pin "P88") (pinfunction "GND9_P88") (pintype "passive"))
      (node (ref "U1") (pin "P9") (pinfunction "GND0_P9") (pintype "passive"))
      (node (ref "U1") (pin "P94") (pinfunction "GND10_P94") (pintype "passive"))
      (node (ref "X1") (pin "3") (pinfunction "2_3") (pintype "passive"))
      (node (ref "X2") (pin "13") (pinfunction "13_13") (pintype "passive"))
      (node (ref "X2") (pin "14") (pinfunction "14_14") (pintype "passive"))
      (node (ref "X2") (pin "17") (pinfunction "17_17") (pintype "passive"))
      (node (ref "X2") (pin "18") (pinfunction "18_18") (pintype "passive"))
      (node (ref "X2") (pin "21") (pinfunction "21_21") (pintype "passive"))
      (node (ref "X2") (pin "4") (pinfunction "4_4") (pintype "passive"))
      (node (ref "X2") (pin "5") (pinfunction "5_5") (pintype "passive"))
      (node (ref "X2") (pin "9") (pinfunction "9_9") (pintype "passive"))
      (node (ref "X3") (pin "3") (pinfunction "3_3") (pintype "passive"))
      (node (ref "X3") (pin "SH2") (pinfunction "PE2_SH2") (pintype "power_in"))
      (node (ref "X4") (pin "8") (pinfunction "F_8") (pintype "passive"))
      (node (ref "X4") (pin "G1") (pinfunction "G1_G1") (pintype "passive"))
      (node (ref "X5") (pin "8") (pinfunction "F_8") (pintype "passive"))
      (node (ref "X5") (pin "G1") (pinfunction "G1_G1") (pintype "passive"))
    )
    (net (code "68") (name "Net-(C1-Pad2)") (class "Default")
      (node (ref "C1") (pin "2") (pinfunction "2_2") (pintype "passive"))
      (node (ref "R23") (pin "2") (pinfunction "2_2") (pintype "passive"))
      (node (ref "R48") (pin "1") (pinfunction "1_1") (pintype "passive"))
    )
    (net (code "69") (name "Net-(C2-Pad1)") (class "Default")
      (node (ref "C2") (pin "1") (pinfunction "1_1") (pintype "passive"))
      (node (ref "R17") (pin "2") (pinfunction "2_2") (pintype "passive"))
      (node (ref "X1") (pin "1") (pinfunction "1_1") (pintype "passive"))
    )
    (net (code "70") (name "Net-(C3-Pad1)") (class "Default")
      (node (ref "C3") (pin "1") (pinfunction "1_1") (pintype "passive"))
      (node (ref "R48") (pin "2") (pinfunction "2_2") (pintype "passive"))
    )
    (net (code "71") (name "Net-(C4-Pad1)") (class "Default")
      (node (ref "C4") (pin "1") (pinfunction "1_1") (pintype "passive"))
      (node (ref "R49") (pin "2") (pinfunction "2_2") (pintype "passive"))
    )
    (net (code "72") (name "Net-(C5-Pad2)") (class "Default")
      (node (ref "C5") (pin "2") (pinfunction "2_2") (pintype "passive"))
      (node (ref "R34") (pin "2") (pinfunction "2_2") (pintype "passive"))
      (node (ref "R49") (pin "1") (pinfunction "1_1") (pintype "passive"))
    )
    (net (code "73") (name "Net-(IC1-CLK)") (class "Default")
      (node (ref "IC1") (pin "3") (pinfunction "CLK_3") (pintype "bidirectional"))
      (node (ref "U1") (pin "P72") (pinfunction "CCLK_P72") (pintype "bidirectional"))
    )
    (net (code "74") (name "Net-(IC1-TDO)") (class "Default")
      (node (ref "IC1") (pin "17") (pinfunction "TDO_17") (pintype "bidirectional"))
      (node (ref "R1") (pin "2") (pinfunction "2_2") (pintype "passive"))
    )
    (net (code "75") (name "Net-(IC1-{slash}CE)") (class "Default")
      (node (ref "IC1") (pin "10") (pinfunction "/CE_10") (pintype "bidirectional"))
      (node (ref "U1") (pin "P71") (pinfunction "DONE_P71") (pintype "bidirectional"))
    )
    (net (code "76") (name "Net-(IC1-{slash}CF)") (class "Default")
      (node (ref "IC1") (pin "7") (pinfunction "/CF_7") (pintype "bidirectional"))
      (node (ref "U1") (pin "P143") (pinfunction "PROG_B_P143") (pintype "bidirectional"))
    )
    (net (code "77") (name "Net-(Q5-B)") (class "Default")
      (node (ref "Q5") (pin "1") (pinfunction "B_1") (pintype "passive"))
      (node (ref "R8") (pin "2") (pinfunction "2_2") (pintype "passive"))
    )
    (net (code "78") (name "Net-(Q5-E)") (class "Default")
      (node (ref "Q5") (pin "2") (pinfunction "E_2") (pintype "passive"))
      (node (ref "R13") (pin "2") (pinfunction "2_2") (pintype "passive"))
      (node (ref "R14") (pin "2") (pinfunction "2_2") (pintype "passive"))
    )
    (net (code "79") (name "Net-(Q6-B)") (class "Default")
      (node (ref "Q6") (pin "1") (pinfunction "B_1") (pintype "passive"))
      (node (ref "R10") (pin "2") (pinfunction "2_2") (pintype "passive"))
      (node (ref "R9") (pin "2") (pinfunction "2_2") (pintype "passive"))
    )
    (net (code "80") (name "Net-(Q6-E)") (class "Default")
      (node (ref "Q6") (pin "2") (pinfunction "E_2") (pintype "passive"))
      (node (ref "R15") (pin "2") (pinfunction "2_2") (pintype "passive"))
      (node (ref "R16") (pin "2") (pinfunction "2_2") (pintype "passive"))
      (node (ref "R20") (pin "2") (pinfunction "2_2") (pintype "passive"))
    )
    (net (code "81") (name "Net-(Q7-B)") (class "Default")
      (node (ref "Q7") (pin "1") (pinfunction "B_1") (pintype "passive"))
      (node (ref "R29") (pin "2") (pinfunction "2_2") (pintype "passive"))
      (node (ref "R30") (pin "2") (pinfunction "2_2") (pintype "passive"))
    )
    (net (code "82") (name "Net-(Q7-E)") (class "Default")
      (node (ref "Q7") (pin "2") (pinfunction "E_2") (pintype "passive"))
      (node (ref "R31") (pin "2") (pinfunction "2_2") (pintype "passive"))
      (node (ref "R32") (pin "2") (pinfunction "2_2") (pintype "passive"))
      (node (ref "R33") (pin "2") (pinfunction "2_2") (pintype "passive"))
    )
    (net (code "83") (name "Net-(Q8-B)") (class "Default")
      (node (ref "Q8") (pin "1") (pinfunction "B_1") (pintype "passive"))
      (node (ref "R24") (pin "2") (pinfunction "2_2") (pintype "passive"))
      (node (ref "R25") (pin "2") (pinfunction "2_2") (pintype "passive"))
    )
    (net (code "84") (name "Net-(Q8-E)") (class "Default")
      (node (ref "Q8") (pin "2") (pinfunction "E_2") (pintype "passive"))
      (node (ref "R26") (pin "2") (pinfunction "2_2") (pintype "passive"))
      (node (ref "R27") (pin "2") (pinfunction "2_2") (pintype "passive"))
      (node (ref "R28") (pin "2") (pinfunction "2_2") (pintype "passive"))
    )
    (net (code "85") (name "Net-(R18-Pad2)") (class "Default")
      (node (ref "R18") (pin "2") (pinfunction "2_2") (pintype "passive"))
      (node (ref "R22") (pin "2") (pinfunction "2_2") (pintype "passive"))
    )
    (net (code "86") (name "Net-(T2-B)") (class "Default")
      (node (ref "C2") (pin "2") (pinfunction "2_2") (pintype "passive"))
      (node (ref "R18") (pin "1") (pinfunction "1_1") (pintype "passive"))
      (node (ref "R19") (pin "2") (pinfunction "2_2") (pintype "passive"))
      (node (ref "T2") (pin "1") (pinfunction "B_1") (pintype "passive"))
    )
    (net (code "87") (name "Net-(U$1-A0)") (class "Default")
      (node (ref "U$1") (pin "P20") (pinfunction "A0_P20") (pintype "bidirectional"))
      (node (ref "U1") (pin "P77") (pinfunction "IO_L20P_3_P77") (pintype "bidirectional"))
    )
    (net (code "88") (name "Net-(U$1-A1)") (class "Default")
      (node (ref "U$1") (pin "P19") (pinfunction "A1_P19") (pintype "bidirectional"))
      (node (ref "U1") (pin "P76") (pinfunction "IO_P76") (pintype "bidirectional"))
    )
    (net (code "89") (name "Net-(U$1-A2)") (class "Default")
      (node (ref "U$1") (pin "P18") (pinfunction "A2_P18") (pintype "bidirectional"))
      (node (ref "U1") (pin "P74") (pinfunction "IO_L01N_3VRP_3_P74") (pintype "bidirectional"))
    )
    (net (code "90") (name "Net-(U$1-A3)") (class "Default")
      (node (ref "U$1") (pin "P17") (pinfunction "A3_P17") (pintype "bidirectional"))
      (node (ref "U1") (pin "P73") (pinfunction "IO_L01P_3VRN_3_P73") (pintype "bidirectional"))
    )
    (net (code "91") (name "Net-(U$1-A4)") (class "Default")
      (node (ref "U$1") (pin "P16") (pinfunction "A4_P16") (pintype "bidirectional"))
      (node (ref "U1") (pin "P108") (pinfunction "IO_L01N_2VRP_2_P108") (pintype "bidirectional"))
    )
    (net (code "92") (name "Net-(U$1-A5)") (class "Default")
      (node (ref "U$1") (pin "P15") (pinfunction "A5_P15") (pintype "bidirectional"))
      (node (ref "U1") (pin "P107") (pinfunction "IO_L01P_2VRN_2_P107") (pintype "bidirectional"))
    )
    (net (code "93") (name "Net-(U$1-A6)") (class "Default")
      (node (ref "U$1") (pin "P14") (pinfunction "A6_P14") (pintype "bidirectional"))
      (node (ref "U1") (pin "P105") (pinfunction "IO_L20N_2_P105") (pintype "bidirectional"))
    )
    (net (code "94") (name "Net-(U$1-A7)") (class "Default")
      (node (ref "U$1") (pin "P13") (pinfunction "A7_P13") (pintype "bidirectional"))
      (node (ref "U1") (pin "P104") (pinfunction "IO_L20P_2_P104") (pintype "bidirectional"))
    )
    (net (code "95") (name "Net-(U$1-A8)") (class "Default")
      (node (ref "U$1") (pin "P3") (pinfunction "A8_P3") (pintype "bidirectional"))
      (node (ref "U1") (pin "P93") (pinfunction "IO_L40N_2_P93") (pintype "bidirectional"))
    )
    (net (code "96") (name "Net-(U$1-A9)") (class "Default")
      (node (ref "U$1") (pin "P2") (pinfunction "A9_P2") (pintype "bidirectional"))
      (node (ref "U1") (pin "P92") (pinfunction "IO_L40P_2VREF_2_P92") (pintype "bidirectional"))
    )
    (net (code "97") (name "Net-(U$1-A10)") (class "Default")
      (node (ref "U$1") (pin "P31") (pinfunction "A10_P31") (pintype "bidirectional"))
      (node (ref "U1") (pin "P87") (pinfunction "IO_L24N_3_P87") (pintype "bidirectional"))
    )
    (net (code "98") (name "Net-(U$1-A11)") (class "Default")
      (node (ref "U$1") (pin "P1") (pinfunction "A11_P1") (pintype "bidirectional"))
      (node (ref "U1") (pin "P90") (pinfunction "IO_L40N_3VREF_3_P90") (pintype "bidirectional"))
    )
    (net (code "99") (name "Net-(U$1-A12)") (class "Default")
      (node (ref "U$1") (pin "P12") (pinfunction "A12_P12") (pintype "bidirectional"))
      (node (ref "U1") (pin "P103") (pinfunction "IO_L21N_2_P103") (pintype "bidirectional"))
    )
    (net (code "100") (name "Net-(U$1-A13)") (class "Default")
      (node (ref "U$1") (pin "P4") (pinfunction "A13_P4") (pintype "bidirectional"))
      (node (ref "U1") (pin "P95") (pinfunction "IO_L24P_2_P95") (pintype "bidirectional"))
    )
    (net (code "101") (name "Net-(U$1-A14)") (class "Default")
      (node (ref "U$1") (pin "P11") (pinfunction "A14_P11") (pintype "bidirectional"))
      (node (ref "U1") (pin "P102") (pinfunction "IO_L21P_2_P102") (pintype "bidirectional"))
    )
    (net (code "102") (name "Net-(U$1-A15)") (class "Default")
      (node (ref "U$1") (pin "P7") (pinfunction "A15_P7") (pintype "bidirectional"))
      (node (ref "U1") (pin "P98") (pinfunction "IO_L23N_2VREF_2_P98") (pintype "bidirectional"))
    )
    (net (code "103") (name "Net-(U$1-A16)") (class "Default")
      (node (ref "U$1") (pin "P10") (pinfunction "A16_P10") (pintype "bidirectional"))
      (node (ref "U1") (pin "P100") (pinfunction "IO_L22N_2_P100") (pintype "bidirectional"))
    )
    (net (code "104") (name "Net-(U$1-A17)") (class "Default")
      (node (ref "U$1") (pin "P6") (pinfunction "A17_P6") (pintype "bidirectional"))
      (node (ref "U1") (pin "P97") (pinfunction "IO_L23P_2_P97") (pintype "bidirectional"))
    )
    (net (code "105") (name "Net-(U$1-A18)") (class "Default")
      (node (ref "U$1") (pin "P9") (pinfunction "A18_P9") (pintype "bidirectional"))
      (node (ref "U1") (pin "P99") (pinfunction "IO_L22P_2_P99") (pintype "bidirectional"))
    )
    (net (code "106") (name "Net-(U$1-DQ0)") (class "Default")
      (node (ref "U$1") (pin "P21") (pinfunction "DQ0_P21") (pintype "bidirectional"))
      (node (ref "U1") (pin "P78") (pinfunction "IO_L20N_3_P78") (pintype "bidirectional"))
    )
    (net (code "107") (name "Net-(U$1-DQ1)") (class "Default")
      (node (ref "U$1") (pin "P22") (pinfunction "DQ1_P22") (pintype "bidirectional"))
      (node (ref "U1") (pin "P79") (pinfunction "IO_L21P_3_P79") (pintype "bidirectional"))
    )
    (net (code "108") (name "Net-(U$1-DQ2)") (class "Default")
      (node (ref "U$1") (pin "P23") (pinfunction "DQ2_P23") (pintype "bidirectional"))
      (node (ref "U1") (pin "P80") (pinfunction "IO_L21N_3_P80") (pintype "bidirectional"))
    )
    (net (code "109") (name "Net-(U$1-DQ3)") (class "Default")
      (node (ref "U$1") (pin "P25") (pinfunction "DQ3_P25") (pintype "bidirectional"))
      (node (ref "U1") (pin "P82") (pinfunction "IO_L22P_3_P82") (pintype "bidirectional"))
    )
    (net (code "110") (name "Net-(U$1-DQ4)") (class "Default")
      (node (ref "U$1") (pin "P26") (pinfunction "DQ4_P26") (pintype "bidirectional"))
      (node (ref "U1") (pin "P83") (pinfunction "IO_L22N_3_P83") (pintype "bidirectional"))
    )
    (net (code "111") (name "Net-(U$1-DQ5)") (class "Default")
      (node (ref "U$1") (pin "P27") (pinfunction "DQ5_P27") (pintype "bidirectional"))
      (node (ref "U1") (pin "P84") (pinfunction "IO_L23P_3VREF_3_P84") (pintype "bidirectional"))
    )
    (net (code "112") (name "Net-(U$1-DQ6)") (class "Default")
      (node (ref "U$1") (pin "P28") (pinfunction "DQ6_P28") (pintype "bidirectional"))
      (node (ref "U1") (pin "P85") (pinfunction "IO_L23N_3_P85") (pintype "bidirectional"))
    )
    (net (code "113") (name "Net-(U$1-DQ7)") (class "Default")
      (node (ref "U$1") (pin "P29") (pinfunction "DQ7_P29") (pintype "bidirectional"))
      (node (ref "U1") (pin "P86") (pinfunction "IO_L24P_3_P86") (pintype "bidirectional"))
    )
    (net (code "114") (name "Net-(U$1-OE)") (class "Default")
      (node (ref "U$1") (pin "P32") (pinfunction "OE_P32") (pintype "bidirectional"))
      (node (ref "U1") (pin "P89") (pinfunction "IO_L40P_3_P89") (pintype "bidirectional"))
    )
    (net (code "115") (name "Net-(U$1-WE)") (class "Default")
      (node (ref "U$1") (pin "P5") (pinfunction "WE_P5") (pintype "bidirectional"))
      (node (ref "U1") (pin "P96") (pinfunction "IO_L24N_2_P96") (pintype "bidirectional"))
    )
    (net (code "116") (name "Net-(U1N-TCK)") (class "Default")
      (node (ref "R2") (pin "1") (pinfunction "1_1") (pintype "passive"))
      (node (ref "U1") (pin "P110") (pinfunction "TCK_P110") (pintype "bidirectional"))
    )
    (net (code "117") (name "Net-(U1N-TDI)") (class "Default")
      (node (ref "R1") (pin "1") (pinfunction "1_1") (pintype "passive"))
      (node (ref "U1") (pin "P144") (pinfunction "TDI_P144") (pintype "bidirectional"))
    )
    (net (code "118") (name "Net-(U1N-TMS)") (class "Default")
      (node (ref "R3") (pin "1") (pinfunction "1_1") (pintype "passive"))
      (node (ref "U1") (pin "P111") (pinfunction "TMS_P111") (pintype "bidirectional"))
    )
    (net (code "119") (name "Net-(X4A-F)") (class "Default")
      (node (ref "R40") (pin "2") (pinfunction "2_2") (pintype "passive"))
      (node (ref "X4") (pin "1") (pinfunction "F_1") (pintype "passive"))
    )
    (net (code "120") (name "Net-(X4B-F)") (class "Default")
      (node (ref "R41") (pin "2") (pinfunction "2_2") (pintype "passive"))
      (node (ref "X4") (pin "2") (pinfunction "F_2") (pintype "passive"))
    )
    (net (code "121") (name "Net-(X4C-F)") (class "Default")
      (node (ref "R42") (pin "2") (pinfunction "2_2") (pintype "passive"))
      (node (ref "X4") (pin "3") (pinfunction "F_3") (pintype "passive"))
    )
    (net (code "122") (name "Net-(X4D-F)") (class "Default")
      (node (ref "R43") (pin "2") (pinfunction "2_2") (pintype "passive"))
      (node (ref "X4") (pin "4") (pinfunction "F_4") (pintype "passive"))
    )
    (net (code "123") (name "Net-(X4F-F)") (class "Default")
      (node (ref "R44") (pin "2") (pinfunction "2_2") (pintype "passive"))
      (node (ref "X4") (pin "6") (pinfunction "F_6") (pintype "passive"))
    )
    (net (code "124") (name "Net-(X4G-F)") (class "Default")
      (node (ref "R45") (pin "2") (pinfunction "2_2") (pintype "passive"))
      (node (ref "X4") (pin "7") (pinfunction "F_7") (pintype "passive"))
    )
    (net (code "125") (name "Net-(X5A-F)") (class "Default")
      (node (ref "R46") (pin "1") (pinfunction "1_1") (pintype "passive"))
      (node (ref "X5") (pin "1") (pinfunction "F_1") (pintype "passive"))
    )
    (net (code "126") (name "Net-(X5B-F)") (class "Default")
      (node (ref "R39") (pin "1") (pinfunction "1_1") (pintype "passive"))
      (node (ref "X5") (pin "2") (pinfunction "F_2") (pintype "passive"))
    )
    (net (code "127") (name "Net-(X5C-F)") (class "Default")
      (node (ref "R38") (pin "1") (pinfunction "1_1") (pintype "passive"))
      (node (ref "X5") (pin "3") (pinfunction "F_3") (pintype "passive"))
    )
    (net (code "128") (name "Net-(X5D-F)") (class "Default")
      (node (ref "R37") (pin "1") (pinfunction "1_1") (pintype "passive"))
      (node (ref "X5") (pin "4") (pinfunction "F_4") (pintype "passive"))
    )
    (net (code "129") (name "Net-(X5F-F)") (class "Default")
      (node (ref "R36") (pin "1") (pinfunction "1_1") (pintype "passive"))
      (node (ref "X5") (pin "6") (pinfunction "F_6") (pintype "passive"))
    )
    (net (code "130") (name "Net-(X5G-F)") (class "Default")
      (node (ref "R35") (pin "1") (pinfunction "1_1") (pintype "passive"))
      (node (ref "X5") (pin "7") (pinfunction "F_7") (pintype "passive"))
    )
    (net (code "131") (name "unconnected-(IC1-NC.1-Pad2)") (class "Default")
      (node (ref "IC1") (pin "2") (pinfunction "NC.1_2") (pintype "bidirectional"))
    )
    (net (code "132") (name "unconnected-(IC1-NC.2-Pad9)") (class "Default")
      (node (ref "IC1") (pin "9") (pinfunction "NC.2_9") (pintype "bidirectional"))
    )
    (net (code "133") (name "unconnected-(IC1-NC.3-Pad12)") (class "Default")
      (node (ref "IC1") (pin "12") (pinfunction "NC.3_12") (pintype "bidirectional"))
    )
    (net (code "134") (name "unconnected-(IC1-NC.4-Pad14)") (class "Default")
      (node (ref "IC1") (pin "14") (pinfunction "NC.4_14") (pintype "bidirectional"))
    )
    (net (code "135") (name "unconnected-(IC1-NC.5-Pad15)") (class "Default")
      (node (ref "IC1") (pin "15") (pinfunction "NC.5_15") (pintype "bidirectional"))
    )
    (net (code "136") (name "unconnected-(IC1-NC.6-Pad16)") (class "Default")
      (node (ref "IC1") (pin "16") (pinfunction "NC.6_16") (pintype "bidirectional"))
    )
    (net (code "137") (name "unconnected-(IC1-{slash}CEO-Pad13)") (class "Default")
      (node (ref "IC1") (pin "13") (pinfunction "/CEO_13") (pintype "bidirectional"))
    )
    (net (code "138") (name "unconnected-(IC3-AVCC-Pad32)") (class "Default")
      (node (ref "IC3") (pin "32") (pinfunction "AVCC_32") (pintype "bidirectional"))
    )
    (net (code "139") (name "unconnected-(IC3-D+-Pad29)") (class "Default")
      (node (ref "IC3") (pin "29") (pinfunction "D+_29") (pintype "bidirectional"))
    )
    (net (code "140") (name "unconnected-(IC3-D--Pad30)") (class "Default")
      (node (ref "IC3") (pin "30") (pinfunction "D-_30") (pintype "bidirectional"))
    )
    (net (code "141") (name "unconnected-(IC3-GND-Pad3)") (class "Default")
      (node (ref "IC3") (pin "3") (pinfunction "GND_3") (pintype "bidirectional"))
    )
    (net (code "142") (name "unconnected-(IC3-PB4(T1{slash}PCINT4)-Pad18)") (class "Default")
      (node (ref "IC3") (pin "18") (pinfunction "PB4(T1/PCINT4)_18") (pintype "bidirectional"))
    )
    (net (code "143") (name "unconnected-(IC3-PB5(PCINT5)-Pad19)") (class "Default")
      (node (ref "IC3") (pin "19") (pinfunction "PB5(PCINT5)_19") (pintype "bidirectional"))
    )
    (net (code "144") (name "unconnected-(IC3-PB6(PCINT6)-Pad20)") (class "Default")
      (node (ref "IC3") (pin "20") (pinfunction "PB6(PCINT6)_20") (pintype "bidirectional"))
    )
    (net (code "145") (name "unconnected-(IC3-PB7(OC0A{slash}OC1C{slash}PCINT7)-Pad21)") (class "Default")
      (node (ref "IC3") (pin "21") (pinfunction "PB7(OC0A/OC1C/PCINT7)_21") (pintype "bidirectional"))
    )
    (net (code "146") (name "unconnected-(IC3-PC2(AIN2{slash}PCIN11)-Pad5)") (class "Default")
      (node (ref "IC3") (pin "5") (pinfunction "PC2(AIN2/PCIN11)_5") (pintype "bidirectional"))
    )
    (net (code "147") (name "unconnected-(IC3-PC4(PCINT10)-Pad26)") (class "Default")
      (node (ref "IC3") (pin "26") (pinfunction "PC4(PCINT10)_26") (pintype "bidirectional"))
    )
    (net (code "148") (name "unconnected-(IC3-PC5(OC1B{slash}PCINT9)-Pad25)") (class "Default")
      (node (ref "IC3") (pin "25") (pinfunction "PC5(OC1B/PCINT9)_25") (pintype "bidirectional"))
    )
    (net (code "149") (name "unconnected-(IC3-PC6(OC1A{slash}PCINT8)-Pad23)") (class "Default")
      (node (ref "IC3") (pin "23") (pinfunction "PC6(OC1A/PCINT8)_23") (pintype "bidirectional"))
    )
    (net (code "150") (name "unconnected-(IC3-PC7(ICP1{slash}INT4{slash}CLKO)-Pad22)") (class "Default")
      (node (ref "IC3") (pin "22") (pinfunction "PC7(ICP1/INT4/CLKO)_22") (pintype "bidirectional"))
    )
    (net (code "151") (name "unconnected-(IC3-PD0(INT0{slash}OC0B)-Pad6)") (class "Default")
      (node (ref "IC3") (pin "6") (pinfunction "PD0(INT0/OC0B)_6") (pintype "bidirectional"))
    )
    (net (code "152") (name "unconnected-(IC3-PD1(INT1{slash}AIN0)-Pad7)") (class "Default")
      (node (ref "IC3") (pin "7") (pinfunction "PD1(INT1/AIN0)_7") (pintype "bidirectional"))
    )
    (net (code "153") (name "unconnected-(IC3-PD4(INT5{slash}AIN3)-Pad10)") (class "Default")
      (node (ref "IC3") (pin "10") (pinfunction "PD4(INT5/AIN3)_10") (pintype "bidirectional"))
    )
    (net (code "154") (name "unconnected-(IC3-PD5(XCK{slash}AIN4{slash}PCINT12)-Pad11)") (class "Default")
      (node (ref "IC3") (pin "11") (pinfunction "PD5(XCK/AIN4/PCINT12)_11") (pintype "bidirectional"))
    )
    (net (code "155") (name "unconnected-(IC3-PD6(INT6{slash}AIN5{slash}RTS)-Pad12)") (class "Default")
      (node (ref "IC3") (pin "12") (pinfunction "PD6(INT6/AIN5/RTS)_12") (pintype "bidirectional"))
    )
    (net (code "156") (name "unconnected-(IC3-UCAP-Pad27)") (class "Default")
      (node (ref "IC3") (pin "27") (pinfunction "UCAP_27") (pintype "bidirectional"))
    )
    (net (code "157") (name "unconnected-(IC3-UGND-Pad28)") (class "Default")
      (node (ref "IC3") (pin "28") (pinfunction "UGND_28") (pintype "bidirectional"))
    )
    (net (code "158") (name "unconnected-(IC3-UVCC-Pad31)") (class "Default")
      (node (ref "IC3") (pin "31") (pinfunction "UVCC_31") (pintype "bidirectional"))
    )
    (net (code "159") (name "unconnected-(IC3-VCC-Pad4)") (class "Default")
      (node (ref "IC3") (pin "4") (pinfunction "VCC_4") (pintype "bidirectional"))
    )
    (net (code "160") (name "unconnected-(IC3-XTAL1-Pad1)") (class "Default")
      (node (ref "IC3") (pin "1") (pinfunction "XTAL1_1") (pintype "bidirectional"))
    )
    (net (code "161") (name "unconnected-(IC3-XTAL2{slash}PC0-Pad2)") (class "Default")
      (node (ref "IC3") (pin "2") (pinfunction "XTAL2/PC0_2") (pintype "bidirectional"))
    )
    (net (code "162") (name "unconnected-(IC3-{slash}RESET(PC1)-Pad24)") (class "Default")
      (node (ref "IC3") (pin "24") (pinfunction "/RESET(PC1)_24") (pintype "bidirectional"))
    )
    (net (code "163") (name "unconnected-(REG1.2-VOUT2-Pad2)") (class "Default")
      (node (ref "REG1.2") (pin "2") (pinfunction "VOUT2_2") (pintype "bidirectional"))
    )
    (net (code "164") (name "unconnected-(U$2-TRI-PadENA)") (class "Default")
      (node (ref "U$2") (pin "ENA") (pinfunction "TRI_ENA") (pintype "input"))
    )
    (net (code "165") (name "unconnected-(U1A-IO_L27P_0-PadP135)") (class "Default")
      (node (ref "U1") (pin "P135") (pinfunction "IO_L27P_0_P135") (pintype "bidirectional"))
    )
    (net (code "166") (name "unconnected-(U1A-IO_L30N_0-PadP132)") (class "Default")
      (node (ref "U1") (pin "P132") (pinfunction "IO_L30N_0_P132") (pintype "bidirectional"))
    )
    (net (code "167") (name "unconnected-(U1A-IO_L30P_0-PadP131)") (class "Default")
      (node (ref "U1") (pin "P131") (pinfunction "IO_L30P_0_P131") (pintype "bidirectional"))
    )
    (net (code "168") (name "unconnected-(U1A-IO_L31N_0-PadP130)") (class "Default")
      (node (ref "U1") (pin "P130") (pinfunction "IO_L31N_0_P130") (pintype "bidirectional"))
    )
    (net (code "169") (name "unconnected-(U1A-IO_L31P_0VREF_0-PadP129)") (class "Default")
      (node (ref "U1") (pin "P129") (pinfunction "IO_L31P_0VREF_0_P129") (pintype "bidirectional"))
    )
    (net (code "170") (name "unconnected-(U1A-IO_L32N_0GCLK7-PadP128)") (class "Default")
      (node (ref "U1") (pin "P128") (pinfunction "IO_L32N_0GCLK7_P128") (pintype "bidirectional"))
    )
    (net (code "171") (name "unconnected-(U1A-IO_L32P_0GCLK6-PadP127)") (class "Default")
      (node (ref "U1") (pin "P127") (pinfunction "IO_L32P_0GCLK6_P127") (pintype "bidirectional"))
    )
    (net (code "172") (name "unconnected-(U1C-IO-PadP116)") (class "Default")
      (node (ref "U1") (pin "P116") (pinfunction "IO_P116") (pintype "bidirectional"))
    )
    (net (code "173") (name "unconnected-(U1C-IO_L01N_1VRP_1-PadP113)") (class "Default")
      (node (ref "U1") (pin "P113") (pinfunction "IO_L01N_1VRP_1_P113") (pintype "bidirectional"))
    )
    (net (code "174") (name "unconnected-(U1C-IO_L01P_1VRN_1-PadP112)") (class "Default")
      (node (ref "U1") (pin "P112") (pinfunction "IO_L01P_1VRN_1_P112") (pintype "bidirectional"))
    )
    (net (code "175") (name "unconnected-(U1C-IO_L28N_1-PadP119)") (class "Default")
      (node (ref "U1") (pin "P119") (pinfunction "IO_L28N_1_P119") (pintype "bidirectional"))
    )
    (net (code "176") (name "unconnected-(U1C-IO_L28P_1-PadP118)") (class "Default")
      (node (ref "U1") (pin "P118") (pinfunction "IO_L28P_1_P118") (pintype "bidirectional"))
    )
    (net (code "177") (name "unconnected-(U1C-IO_L31N_1VREF_1-PadP123)") (class "Default")
      (node (ref "U1") (pin "P123") (pinfunction "IO_L31N_1VREF_1_P123") (pintype "bidirectional"))
    )
    (net (code "178") (name "unconnected-(U1C-IO_L31P_1-PadP122)") (class "Default")
      (node (ref "U1") (pin "P122") (pinfunction "IO_L31P_1_P122") (pintype "bidirectional"))
    )
    (net (code "179") (name "unconnected-(U1C-IO_L32N_1GCLK5-PadP125)") (class "Default")
      (node (ref "U1") (pin "P125") (pinfunction "IO_L32N_1GCLK5_P125") (pintype "bidirectional"))
    )
    (net (code "180") (name "unconnected-(U1C-IO_L32P_1GCLK4-PadP124)") (class "Default")
      (node (ref "U1") (pin "P124") (pinfunction "IO_L32P_1GCLK4_P124") (pintype "bidirectional"))
    )
    (net (code "181") (name "unconnected-(U1J-IO_L01N_6VRP_6-PadP36)") (class "Default")
      (node (ref "U1") (pin "P36") (pinfunction "IO_L01N_6VRP_6_P36") (pintype "bidirectional"))
    )
    (net (code "182") (name "unconnected-(U1J-IO_L01P_6VRN_6-PadP35)") (class "Default")
      (node (ref "U1") (pin "P35") (pinfunction "IO_L01P_6VRN_6_P35") (pintype "bidirectional"))
    )
    (net (code "183") (name "unconnected-(U1J-IO_L20N_6-PadP33)") (class "Default")
      (node (ref "U1") (pin "P33") (pinfunction "IO_L20N_6_P33") (pintype "bidirectional"))
    )
    (net (code "184") (name "unconnected-(U1J-IO_L20P_6-PadP32)") (class "Default")
      (node (ref "U1") (pin "P32") (pinfunction "IO_L20P_6_P32") (pintype "bidirectional"))
    )
    (net (code "185") (name "unconnected-(U1J-IO_L21N_6-PadP31)") (class "Default")
      (node (ref "U1") (pin "P31") (pinfunction "IO_L21N_6_P31") (pintype "bidirectional"))
    )
    (net (code "186") (name "unconnected-(U1J-IO_L21P_6-PadP30)") (class "Default")
      (node (ref "U1") (pin "P30") (pinfunction "IO_L21P_6_P30") (pintype "bidirectional"))
    )
    (net (code "187") (name "unconnected-(U1J-IO_L22N_6-PadP28)") (class "Default")
      (node (ref "U1") (pin "P28") (pinfunction "IO_L22N_6_P28") (pintype "bidirectional"))
    )
    (net (code "188") (name "unconnected-(U1J-IO_L22P_6-PadP27)") (class "Default")
      (node (ref "U1") (pin "P27") (pinfunction "IO_L22P_6_P27") (pintype "bidirectional"))
    )
    (net (code "189") (name "unconnected-(U1J-IO_L23N_6-PadP26)") (class "Default")
      (node (ref "U1") (pin "P26") (pinfunction "IO_L23N_6_P26") (pintype "bidirectional"))
    )
    (net (code "190") (name "unconnected-(U1J-IO_L23P_6-PadP25)") (class "Default")
      (node (ref "U1") (pin "P25") (pinfunction "IO_L23P_6_P25") (pintype "bidirectional"))
    )
    (net (code "191") (name "unconnected-(U1J-IO_L24N_6VREF_6-PadP24)") (class "Default")
      (node (ref "U1") (pin "P24") (pinfunction "IO_L24N_6VREF_6_P24") (pintype "bidirectional"))
    )
    (net (code "192") (name "unconnected-(U1J-IO_L24P_6-PadP23)") (class "Default")
      (node (ref "U1") (pin "P23") (pinfunction "IO_L24P_6_P23") (pintype "bidirectional"))
    )
    (net (code "193") (name "unconnected-(U1J-IO_L40N_6-PadP21)") (class "Default")
      (node (ref "U1") (pin "P21") (pinfunction "IO_L40N_6_P21") (pintype "bidirectional"))
    )
    (net (code "194") (name "unconnected-(U1J-IO_L40P_6VREF_6-PadP20)") (class "Default")
      (node (ref "U1") (pin "P20") (pinfunction "IO_L40P_6VREF_6_P20") (pintype "bidirectional"))
    )
    (net (code "195") (name "unconnected-(U1L-IOVREF_7-PadP4)") (class "Default")
      (node (ref "U1") (pin "P4") (pinfunction "IOVREF_7_P4") (pintype "bidirectional"))
    )
    (net (code "196") (name "unconnected-(U1L-IO_L01N_7VRP_7-PadP2)") (class "Default")
      (node (ref "U1") (pin "P2") (pinfunction "IO_L01N_7VRP_7_P2") (pintype "bidirectional"))
    )
    (net (code "197") (name "unconnected-(U1L-IO_L01P_7VRN_7-PadP1)") (class "Default")
      (node (ref "U1") (pin "P1") (pinfunction "IO_L01P_7VRN_7_P1") (pintype "bidirectional"))
    )
    (net (code "198") (name "unconnected-(U1L-IO_L20N_7-PadP6)") (class "Default")
      (node (ref "U1") (pin "P6") (pinfunction "IO_L20N_7_P6") (pintype "bidirectional"))
    )
    (net (code "199") (name "unconnected-(U1L-IO_L20P_7-PadP5)") (class "Default")
      (node (ref "U1") (pin "P5") (pinfunction "IO_L20P_7_P5") (pintype "bidirectional"))
    )
    (net (code "200") (name "unconnected-(U1L-IO_L21N_7-PadP8)") (class "Default")
      (node (ref "U1") (pin "P8") (pinfunction "IO_L21N_7_P8") (pintype "bidirectional"))
    )
    (net (code "201") (name "unconnected-(U1L-IO_L21P_7-PadP7)") (class "Default")
      (node (ref "U1") (pin "P7") (pinfunction "IO_L21P_7_P7") (pintype "bidirectional"))
    )
    (net (code "202") (name "unconnected-(U1L-IO_L22N_7-PadP11)") (class "Default")
      (node (ref "U1") (pin "P11") (pinfunction "IO_L22N_7_P11") (pintype "bidirectional"))
    )
    (net (code "203") (name "unconnected-(U1L-IO_L22P_7-PadP10)") (class "Default")
      (node (ref "U1") (pin "P10") (pinfunction "IO_L22P_7_P10") (pintype "bidirectional"))
    )
    (net (code "204") (name "unconnected-(U1L-IO_L23N_7-PadP13)") (class "Default")
      (node (ref "U1") (pin "P13") (pinfunction "IO_L23N_7_P13") (pintype "bidirectional"))
    )
    (net (code "205") (name "unconnected-(U1L-IO_L23P_7-PadP12)") (class "Default")
      (node (ref "U1") (pin "P12") (pinfunction "IO_L23P_7_P12") (pintype "bidirectional"))
    )
    (net (code "206") (name "unconnected-(U1L-IO_L24N_7-PadP15)") (class "Default")
      (node (ref "U1") (pin "P15") (pinfunction "IO_L24N_7_P15") (pintype "bidirectional"))
    )
    (net (code "207") (name "unconnected-(U1L-IO_L24P_7-PadP14)") (class "Default")
      (node (ref "U1") (pin "P14") (pinfunction "IO_L24P_7_P14") (pintype "bidirectional"))
    )
    (net (code "208") (name "unconnected-(U1L-IO_L40N_7VREF_7-PadP18)") (class "Default")
      (node (ref "U1") (pin "P18") (pinfunction "IO_L40N_7VREF_7_P18") (pintype "bidirectional"))
    )
    (net (code "209") (name "unconnected-(U1L-IO_L40P_7-PadP17)") (class "Default")
      (node (ref "U1") (pin "P17") (pinfunction "IO_L40P_7_P17") (pintype "bidirectional"))
    )
    (net (code "210") (name "unconnected-(U1N-HSWAP_EN-PadP142)") (class "Default")
      (node (ref "U1") (pin "P142") (pinfunction "HSWAP_EN_P142") (pintype "bidirectional"))
    )
    (net (code "211") (name "unconnected-(X1-3-Pad2)") (class "Default")
      (node (ref "X1") (pin "2") (pinfunction "3_2") (pintype "passive"))
    )
    (net (code "212") (name "unconnected-(X2-Pad10)") (class "Default")
      (node (ref "X2") (pin "10") (pinfunction "10_10") (pintype "passive"))
    )
    (net (code "213") (name "unconnected-(X2-Pad12)") (class "Default")
      (node (ref "X2") (pin "12") (pinfunction "12_12") (pintype "passive"))
    )
    (net (code "214") (name "unconnected-(X3-Pad2)") (class "Default")
      (node (ref "X3") (pin "2") (pinfunction "2_2") (pintype "passive"))
    )
    (net (code "215") (name "unconnected-(X3-Pad8)") (class "Default")
      (node (ref "X3") (pin "8") (pinfunction "8_8") (pintype "passive"))
    )
    (net (code "216") (name "unconnected-(X4-PadG2)") (class "Default")
      (node (ref "X4") (pin "G2") (pinfunction "G2_G2") (pintype "passive"))
    )
    (net (code "217") (name "unconnected-(X5-PadG2)") (class "Default")
      (node (ref "X5") (pin "G2") (pinfunction "G2_G2") (pintype "passive"))
    )
  )
)
